# STM32_Peripherals.net
KiCad netlist of a schematic drawn in Altium Designer
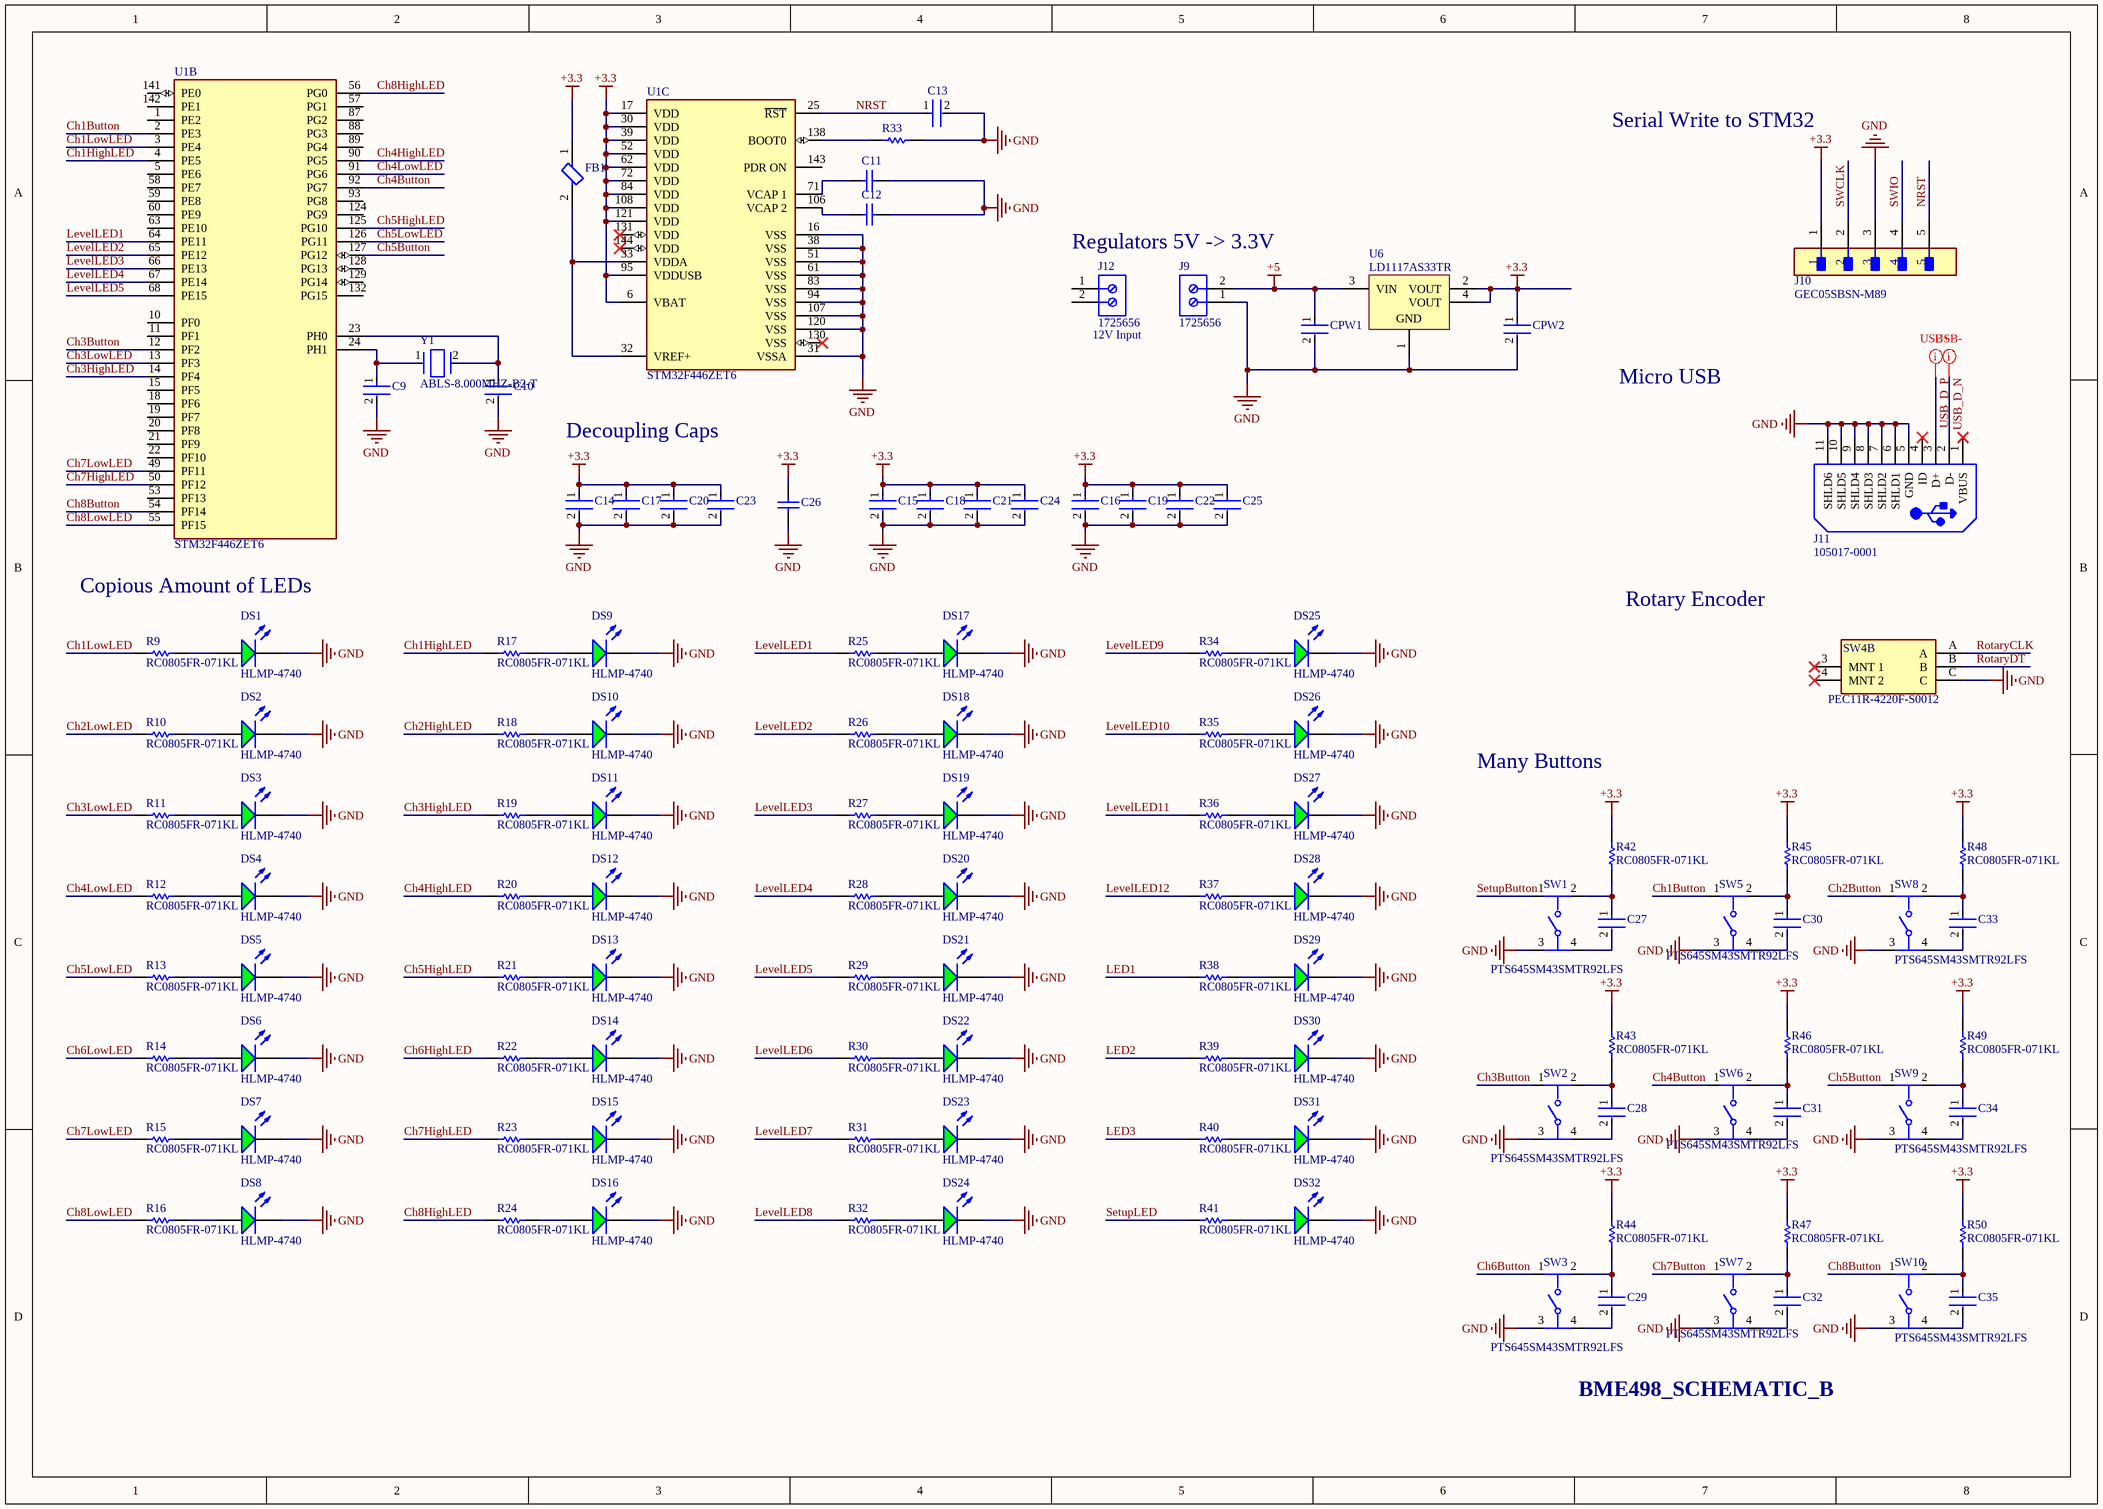
[diagram p0: STM32_Peripherals.SchDoc]

(export (version "E")
  (design (tool "Eeschema 10.0.6"))
  (components
    (comp (ref "C9")
      (value "C0805C439C5GACTU")
      (footprint "FP-C0805C-DN-MFG")
      (description "CAP CER 4.3PF 50V NP0 0805")
      (fields
        (field (name "OCTOPART") "https://octopart.com/c0805c439c5gactu-kemet-9144293")
        (field (name "MANUFACTURER") "KEMET")
      )
      (libsource (lib "Altium Content Vault") (part "b4654b650e69147ec39a6b967a45e02"))
    )
    (comp (ref "C10")
      (value "C0805C439C5GACTU")
      (footprint "FP-C0805C-DN-MFG")
      (description "CAP CER 4.3PF 50V NP0 0805")
      (fields
        (field (name "OCTOPART") "https://octopart.com/c0805c439c5gactu-kemet-9144293")
        (field (name "MANUFACTURER") "KEMET")
      )
      (libsource (lib "Altium Content Vault") (part "b4654b650e69147ec39a6b967a45e02"))
    )
    (comp (ref "C11")
      (value "GRM21BR71C225KA12L")
      (footprint "CAPC2013X135X50ML10T20")
      (fields (field (name "MANUFACTURER") "Murata"))
      (libsource (lib "Altium Content Vault") (part "CAP"))
    )
    (comp (ref "C12")
      (value "GRM21BR71C225KA12L")
      (footprint "CAPC2013X135X50ML10T20")
      (fields (field (name "MANUFACTURER") "Murata"))
      (libsource (lib "Altium Content Vault") (part "CAP"))
    )
    (comp (ref "C13")
      (value "CC0805KRX7R9BB104")
      (footprint "FP-CC0805-0_85-MFG")
      (description "CAP CER 0.1UF 50V X7R 0805")
      (fields (field (name "TOLERANCE") "0.1") (field (name "MANUFACTURER") "Yageo"))
      (libsource (lib "Altium Content Vault") (part "11868f565c42a9108669ba33697ecf6"))
    )
    (comp (ref "C14")
      (value "CC0805KRX7R9BB104")
      (footprint "FP-CC0805-0_85-MFG")
      (description "CAP CER 0.1UF 50V X7R 0805")
      (fields (field (name "TOLERANCE") "0.1") (field (name "MANUFACTURER") "Yageo"))
      (libsource (lib "Altium Content Vault") (part "11868f565c42a9108669ba33697ecf6"))
    )
    (comp (ref "C15")
      (value "CC0805KRX7R9BB104")
      (footprint "FP-CC0805-0_85-MFG")
      (description "CAP CER 0.1UF 50V X7R 0805")
      (fields (field (name "TOLERANCE") "0.1") (field (name "MANUFACTURER") "Yageo"))
      (libsource (lib "Altium Content Vault") (part "11868f565c42a9108669ba33697ecf6"))
    )
    (comp (ref "C16")
      (value "CC0805KRX7R9BB104")
      (footprint "FP-CC0805-0_85-MFG")
      (description "CAP CER 0.1UF 50V X7R 0805")
      (fields (field (name "TOLERANCE") "0.1") (field (name "MANUFACTURER") "Yageo"))
      (libsource (lib "Altium Content Vault") (part "11868f565c42a9108669ba33697ecf6"))
    )
    (comp (ref "C17")
      (value "CC0805KRX7R9BB104")
      (footprint "FP-CC0805-0_85-MFG")
      (description "CAP CER 0.1UF 50V X7R 0805")
      (fields (field (name "TOLERANCE") "0.1") (field (name "MANUFACTURER") "Yageo"))
      (libsource (lib "Altium Content Vault") (part "11868f565c42a9108669ba33697ecf6"))
    )
    (comp (ref "C18")
      (value "CC0805KRX7R9BB104")
      (footprint "FP-CC0805-0_85-MFG")
      (description "CAP CER 0.1UF 50V X7R 0805")
      (fields (field (name "TOLERANCE") "0.1") (field (name "MANUFACTURER") "Yageo"))
      (libsource (lib "Altium Content Vault") (part "11868f565c42a9108669ba33697ecf6"))
    )
    (comp (ref "C19")
      (value "CC0805KRX7R9BB104")
      (footprint "FP-CC0805-0_85-MFG")
      (description "CAP CER 0.1UF 50V X7R 0805")
      (fields (field (name "TOLERANCE") "0.1") (field (name "MANUFACTURER") "Yageo"))
      (libsource (lib "Altium Content Vault") (part "11868f565c42a9108669ba33697ecf6"))
    )
    (comp (ref "C20")
      (value "CC0805KRX7R9BB104")
      (footprint "FP-CC0805-0_85-MFG")
      (description "CAP CER 0.1UF 50V X7R 0805")
      (fields (field (name "TOLERANCE") "0.1") (field (name "MANUFACTURER") "Yageo"))
      (libsource (lib "Altium Content Vault") (part "11868f565c42a9108669ba33697ecf6"))
    )
    (comp (ref "C21")
      (value "CC0805KRX7R9BB104")
      (footprint "FP-CC0805-0_85-MFG")
      (description "CAP CER 0.1UF 50V X7R 0805")
      (fields (field (name "TOLERANCE") "0.1") (field (name "MANUFACTURER") "Yageo"))
      (libsource (lib "Altium Content Vault") (part "11868f565c42a9108669ba33697ecf6"))
    )
    (comp (ref "C22")
      (value "CC0805KRX7R9BB104")
      (footprint "FP-CC0805-0_85-MFG")
      (description "CAP CER 0.1UF 50V X7R 0805")
      (fields (field (name "TOLERANCE") "0.1") (field (name "MANUFACTURER") "Yageo"))
      (libsource (lib "Altium Content Vault") (part "11868f565c42a9108669ba33697ecf6"))
    )
    (comp (ref "C23")
      (value "CC0805KRX7R9BB104")
      (footprint "FP-CC0805-0_85-MFG")
      (description "CAP CER 0.1UF 50V X7R 0805")
      (fields (field (name "TOLERANCE") "0.1") (field (name "MANUFACTURER") "Yageo"))
      (libsource (lib "Altium Content Vault") (part "11868f565c42a9108669ba33697ecf6"))
    )
    (comp (ref "C24")
      (value "CC0805KRX7R9BB104")
      (footprint "FP-CC0805-0_85-MFG")
      (description "CAP CER 0.1UF 50V X7R 0805")
      (fields (field (name "TOLERANCE") "0.1") (field (name "MANUFACTURER") "Yageo"))
      (libsource (lib "Altium Content Vault") (part "11868f565c42a9108669ba33697ecf6"))
    )
    (comp (ref "C25")
      (value "CC0805KRX7R9BB104")
      (footprint "FP-CC0805-0_85-MFG")
      (description "CAP CER 0.1UF 50V X7R 0805")
      (fields (field (name "TOLERANCE") "0.1") (field (name "MANUFACTURER") "Yageo"))
      (libsource (lib "Altium Content Vault") (part "11868f565c42a9108669ba33697ecf6"))
    )
    (comp (ref "C26")
      (value "GRM21BR61C475KA88L")
      (footprint "CAPC2013X135X45LL10T25")
      (description "Chip Capacitor, 4.7 uF, +/- 10%, 16 V, -55 to 85 degC, 0805 (2012 Metric), RoHS, Tape and Reel")
      (fields (field (name "TOLERANCE") "10%"))
      (libsource (lib "Altium Content Vault") (part "CAP-NP-2"))
    )
    (comp (ref "C27")
      (value "CC0805KRX7R9BB104")
      (footprint "FP-CC0805-0_85-MFG")
      (description "CAP CER 0.1UF 50V X7R 0805")
      (fields (field (name "TOLERANCE") "0.1") (field (name "MANUFACTURER") "Yageo"))
      (libsource (lib "Altium Content Vault") (part "11868f565c42a9108669ba33697ecf6"))
    )
    (comp (ref "C28")
      (value "CC0805KRX7R9BB104")
      (footprint "FP-CC0805-0_85-MFG")
      (description "CAP CER 0.1UF 50V X7R 0805")
      (fields (field (name "TOLERANCE") "0.1") (field (name "MANUFACTURER") "Yageo"))
      (libsource (lib "Altium Content Vault") (part "11868f565c42a9108669ba33697ecf6"))
    )
    (comp (ref "C29")
      (value "CC0805KRX7R9BB104")
      (footprint "FP-CC0805-0_85-MFG")
      (description "CAP CER 0.1UF 50V X7R 0805")
      (fields (field (name "TOLERANCE") "0.1") (field (name "MANUFACTURER") "Yageo"))
      (libsource (lib "Altium Content Vault") (part "11868f565c42a9108669ba33697ecf6"))
    )
    (comp (ref "C30")
      (value "CC0805KRX7R9BB104")
      (footprint "FP-CC0805-0_85-MFG")
      (description "CAP CER 0.1UF 50V X7R 0805")
      (fields (field (name "TOLERANCE") "0.1") (field (name "MANUFACTURER") "Yageo"))
      (libsource (lib "Altium Content Vault") (part "11868f565c42a9108669ba33697ecf6"))
    )
    (comp (ref "C31")
      (value "CC0805KRX7R9BB104")
      (footprint "FP-CC0805-0_85-MFG")
      (description "CAP CER 0.1UF 50V X7R 0805")
      (fields (field (name "TOLERANCE") "0.1") (field (name "MANUFACTURER") "Yageo"))
      (libsource (lib "Altium Content Vault") (part "11868f565c42a9108669ba33697ecf6"))
    )
    (comp (ref "C32")
      (value "CC0805KRX7R9BB104")
      (footprint "FP-CC0805-0_85-MFG")
      (description "CAP CER 0.1UF 50V X7R 0805")
      (fields (field (name "TOLERANCE") "0.1") (field (name "MANUFACTURER") "Yageo"))
      (libsource (lib "Altium Content Vault") (part "11868f565c42a9108669ba33697ecf6"))
    )
    (comp (ref "C33")
      (value "CC0805KRX7R9BB104")
      (footprint "FP-CC0805-0_85-MFG")
      (description "CAP CER 0.1UF 50V X7R 0805")
      (fields (field (name "TOLERANCE") "0.1") (field (name "MANUFACTURER") "Yageo"))
      (libsource (lib "Altium Content Vault") (part "11868f565c42a9108669ba33697ecf6"))
    )
    (comp (ref "C34")
      (value "CC0805KRX7R9BB104")
      (footprint "FP-CC0805-0_85-MFG")
      (description "CAP CER 0.1UF 50V X7R 0805")
      (fields (field (name "TOLERANCE") "0.1") (field (name "MANUFACTURER") "Yageo"))
      (libsource (lib "Altium Content Vault") (part "11868f565c42a9108669ba33697ecf6"))
    )
    (comp (ref "C35")
      (value "CC0805KRX7R9BB104")
      (footprint "FP-CC0805-0_85-MFG")
      (description "CAP CER 0.1UF 50V X7R 0805")
      (fields (field (name "TOLERANCE") "0.1") (field (name "MANUFACTURER") "Yageo"))
      (libsource (lib "Altium Content Vault") (part "11868f565c42a9108669ba33697ecf6"))
    )
    (comp (ref "CPW1")
      (value "CC0805KRX7R9BB104")
      (footprint "FP-CC0805-0_85-MFG")
      (description "CAP CER 0.1UF 50V X7R 0805")
      (fields (field (name "TOLERANCE") "0.1") (field (name "MANUFACTURER") "Yageo"))
      (libsource (lib "Altium Content Vault") (part "11868f565c42a9108669ba33697ecf6"))
    )
    (comp (ref "CPW2")
      (value "CC0805KRX7R9BB104")
      (footprint "FP-CC0805-0_85-MFG")
      (description "CAP CER 0.1UF 50V X7R 0805")
      (fields (field (name "TOLERANCE") "0.1") (field (name "MANUFACTURER") "Yageo"))
      (libsource (lib "Altium Content Vault") (part "11868f565c42a9108669ba33697ecf6"))
    )
    (comp (ref "DS1")
      (value "HLMP-4740")
      (footprint "AVAG-HLMP-4740")
      (description "T-1 3/4 (5 mm) Low Current LED Lamp, Green, 1.9 V, -20 to 100 degC, 2-Pin THD, RoHS, Bulk")
      (fields (field (name "MANUFACTURER") "AvagoTechnologies"))
      (libsource (lib "Altium Content Vault") (part "LED-GREEN-AK-2"))
    )
    (comp (ref "DS2")
      (value "HLMP-4740")
      (footprint "AVAG-HLMP-4740")
      (description "T-1 3/4 (5 mm) Low Current LED Lamp, Green, 1.9 V, -20 to 100 degC, 2-Pin THD, RoHS, Bulk")
      (fields (field (name "MANUFACTURER") "AvagoTechnologies"))
      (libsource (lib "Altium Content Vault") (part "LED-GREEN-AK-2"))
    )
    (comp (ref "DS3")
      (value "HLMP-4740")
      (footprint "AVAG-HLMP-4740")
      (description "T-1 3/4 (5 mm) Low Current LED Lamp, Green, 1.9 V, -20 to 100 degC, 2-Pin THD, RoHS, Bulk")
      (fields (field (name "MANUFACTURER") "AvagoTechnologies"))
      (libsource (lib "Altium Content Vault") (part "LED-GREEN-AK-2"))
    )
    (comp (ref "DS4")
      (value "HLMP-4740")
      (footprint "AVAG-HLMP-4740")
      (description "T-1 3/4 (5 mm) Low Current LED Lamp, Green, 1.9 V, -20 to 100 degC, 2-Pin THD, RoHS, Bulk")
      (fields (field (name "MANUFACTURER") "AvagoTechnologies"))
      (libsource (lib "Altium Content Vault") (part "LED-GREEN-AK-2"))
    )
    (comp (ref "DS5")
      (value "HLMP-4740")
      (footprint "AVAG-HLMP-4740")
      (description "T-1 3/4 (5 mm) Low Current LED Lamp, Green, 1.9 V, -20 to 100 degC, 2-Pin THD, RoHS, Bulk")
      (fields (field (name "MANUFACTURER") "AvagoTechnologies"))
      (libsource (lib "Altium Content Vault") (part "LED-GREEN-AK-2"))
    )
    (comp (ref "DS6")
      (value "HLMP-4740")
      (footprint "AVAG-HLMP-4740")
      (description "T-1 3/4 (5 mm) Low Current LED Lamp, Green, 1.9 V, -20 to 100 degC, 2-Pin THD, RoHS, Bulk")
      (fields (field (name "MANUFACTURER") "AvagoTechnologies"))
      (libsource (lib "Altium Content Vault") (part "LED-GREEN-AK-2"))
    )
    (comp (ref "DS7")
      (value "HLMP-4740")
      (footprint "AVAG-HLMP-4740")
      (description "T-1 3/4 (5 mm) Low Current LED Lamp, Green, 1.9 V, -20 to 100 degC, 2-Pin THD, RoHS, Bulk")
      (fields (field (name "MANUFACTURER") "AvagoTechnologies"))
      (libsource (lib "Altium Content Vault") (part "LED-GREEN-AK-2"))
    )
    (comp (ref "DS8")
      (value "HLMP-4740")
      (footprint "AVAG-HLMP-4740")
      (description "T-1 3/4 (5 mm) Low Current LED Lamp, Green, 1.9 V, -20 to 100 degC, 2-Pin THD, RoHS, Bulk")
      (fields (field (name "MANUFACTURER") "AvagoTechnologies"))
      (libsource (lib "Altium Content Vault") (part "LED-GREEN-AK-2"))
    )
    (comp (ref "DS9")
      (value "HLMP-4740")
      (footprint "AVAG-HLMP-4740")
      (description "T-1 3/4 (5 mm) Low Current LED Lamp, Green, 1.9 V, -20 to 100 degC, 2-Pin THD, RoHS, Bulk")
      (fields (field (name "MANUFACTURER") "AvagoTechnologies"))
      (libsource (lib "Altium Content Vault") (part "LED-GREEN-AK-2"))
    )
    (comp (ref "DS10")
      (value "HLMP-4740")
      (footprint "AVAG-HLMP-4740")
      (description "T-1 3/4 (5 mm) Low Current LED Lamp, Green, 1.9 V, -20 to 100 degC, 2-Pin THD, RoHS, Bulk")
      (fields (field (name "MANUFACTURER") "AvagoTechnologies"))
      (libsource (lib "Altium Content Vault") (part "LED-GREEN-AK-2"))
    )
    (comp (ref "DS11")
      (value "HLMP-4740")
      (footprint "AVAG-HLMP-4740")
      (description "T-1 3/4 (5 mm) Low Current LED Lamp, Green, 1.9 V, -20 to 100 degC, 2-Pin THD, RoHS, Bulk")
      (fields (field (name "MANUFACTURER") "AvagoTechnologies"))
      (libsource (lib "Altium Content Vault") (part "LED-GREEN-AK-2"))
    )
    (comp (ref "DS12")
      (value "HLMP-4740")
      (footprint "AVAG-HLMP-4740")
      (description "T-1 3/4 (5 mm) Low Current LED Lamp, Green, 1.9 V, -20 to 100 degC, 2-Pin THD, RoHS, Bulk")
      (fields (field (name "MANUFACTURER") "AvagoTechnologies"))
      (libsource (lib "Altium Content Vault") (part "LED-GREEN-AK-2"))
    )
    (comp (ref "DS13")
      (value "HLMP-4740")
      (footprint "AVAG-HLMP-4740")
      (description "T-1 3/4 (5 mm) Low Current LED Lamp, Green, 1.9 V, -20 to 100 degC, 2-Pin THD, RoHS, Bulk")
      (fields (field (name "MANUFACTURER") "AvagoTechnologies"))
      (libsource (lib "Altium Content Vault") (part "LED-GREEN-AK-2"))
    )
    (comp (ref "DS14")
      (value "HLMP-4740")
      (footprint "AVAG-HLMP-4740")
      (description "T-1 3/4 (5 mm) Low Current LED Lamp, Green, 1.9 V, -20 to 100 degC, 2-Pin THD, RoHS, Bulk")
      (fields (field (name "MANUFACTURER") "AvagoTechnologies"))
      (libsource (lib "Altium Content Vault") (part "LED-GREEN-AK-2"))
    )
    (comp (ref "DS15")
      (value "HLMP-4740")
      (footprint "AVAG-HLMP-4740")
      (description "T-1 3/4 (5 mm) Low Current LED Lamp, Green, 1.9 V, -20 to 100 degC, 2-Pin THD, RoHS, Bulk")
      (fields (field (name "MANUFACTURER") "AvagoTechnologies"))
      (libsource (lib "Altium Content Vault") (part "LED-GREEN-AK-2"))
    )
    (comp (ref "DS16")
      (value "HLMP-4740")
      (footprint "AVAG-HLMP-4740")
      (description "T-1 3/4 (5 mm) Low Current LED Lamp, Green, 1.9 V, -20 to 100 degC, 2-Pin THD, RoHS, Bulk")
      (fields (field (name "MANUFACTURER") "AvagoTechnologies"))
      (libsource (lib "Altium Content Vault") (part "LED-GREEN-AK-2"))
    )
    (comp (ref "DS17")
      (value "HLMP-4740")
      (footprint "AVAG-HLMP-4740")
      (description "T-1 3/4 (5 mm) Low Current LED Lamp, Green, 1.9 V, -20 to 100 degC, 2-Pin THD, RoHS, Bulk")
      (fields (field (name "MANUFACTURER") "AvagoTechnologies"))
      (libsource (lib "Altium Content Vault") (part "LED-GREEN-AK-2"))
    )
    (comp (ref "DS18")
      (value "HLMP-4740")
      (footprint "AVAG-HLMP-4740")
      (description "T-1 3/4 (5 mm) Low Current LED Lamp, Green, 1.9 V, -20 to 100 degC, 2-Pin THD, RoHS, Bulk")
      (fields (field (name "MANUFACTURER") "AvagoTechnologies"))
      (libsource (lib "Altium Content Vault") (part "LED-GREEN-AK-2"))
    )
    (comp (ref "DS19")
      (value "HLMP-4740")
      (footprint "AVAG-HLMP-4740")
      (description "T-1 3/4 (5 mm) Low Current LED Lamp, Green, 1.9 V, -20 to 100 degC, 2-Pin THD, RoHS, Bulk")
      (fields (field (name "MANUFACTURER") "AvagoTechnologies"))
      (libsource (lib "Altium Content Vault") (part "LED-GREEN-AK-2"))
    )
    (comp (ref "DS20")
      (value "HLMP-4740")
      (footprint "AVAG-HLMP-4740")
      (description "T-1 3/4 (5 mm) Low Current LED Lamp, Green, 1.9 V, -20 to 100 degC, 2-Pin THD, RoHS, Bulk")
      (fields (field (name "MANUFACTURER") "AvagoTechnologies"))
      (libsource (lib "Altium Content Vault") (part "LED-GREEN-AK-2"))
    )
    (comp (ref "DS21")
      (value "HLMP-4740")
      (footprint "AVAG-HLMP-4740")
      (description "T-1 3/4 (5 mm) Low Current LED Lamp, Green, 1.9 V, -20 to 100 degC, 2-Pin THD, RoHS, Bulk")
      (fields (field (name "MANUFACTURER") "AvagoTechnologies"))
      (libsource (lib "Altium Content Vault") (part "LED-GREEN-AK-2"))
    )
    (comp (ref "DS22")
      (value "HLMP-4740")
      (footprint "AVAG-HLMP-4740")
      (description "T-1 3/4 (5 mm) Low Current LED Lamp, Green, 1.9 V, -20 to 100 degC, 2-Pin THD, RoHS, Bulk")
      (fields (field (name "MANUFACTURER") "AvagoTechnologies"))
      (libsource (lib "Altium Content Vault") (part "LED-GREEN-AK-2"))
    )
    (comp (ref "DS23")
      (value "HLMP-4740")
      (footprint "AVAG-HLMP-4740")
      (description "T-1 3/4 (5 mm) Low Current LED Lamp, Green, 1.9 V, -20 to 100 degC, 2-Pin THD, RoHS, Bulk")
      (fields (field (name "MANUFACTURER") "AvagoTechnologies"))
      (libsource (lib "Altium Content Vault") (part "LED-GREEN-AK-2"))
    )
    (comp (ref "DS24")
      (value "HLMP-4740")
      (footprint "AVAG-HLMP-4740")
      (description "T-1 3/4 (5 mm) Low Current LED Lamp, Green, 1.9 V, -20 to 100 degC, 2-Pin THD, RoHS, Bulk")
      (fields (field (name "MANUFACTURER") "AvagoTechnologies"))
      (libsource (lib "Altium Content Vault") (part "LED-GREEN-AK-2"))
    )
    (comp (ref "DS25")
      (value "HLMP-4740")
      (footprint "AVAG-HLMP-4740")
      (description "T-1 3/4 (5 mm) Low Current LED Lamp, Green, 1.9 V, -20 to 100 degC, 2-Pin THD, RoHS, Bulk")
      (fields (field (name "MANUFACTURER") "AvagoTechnologies"))
      (libsource (lib "Altium Content Vault") (part "LED-GREEN-AK-2"))
    )
    (comp (ref "DS26")
      (value "HLMP-4740")
      (footprint "AVAG-HLMP-4740")
      (description "T-1 3/4 (5 mm) Low Current LED Lamp, Green, 1.9 V, -20 to 100 degC, 2-Pin THD, RoHS, Bulk")
      (fields (field (name "MANUFACTURER") "AvagoTechnologies"))
      (libsource (lib "Altium Content Vault") (part "LED-GREEN-AK-2"))
    )
    (comp (ref "DS27")
      (value "HLMP-4740")
      (footprint "AVAG-HLMP-4740")
      (description "T-1 3/4 (5 mm) Low Current LED Lamp, Green, 1.9 V, -20 to 100 degC, 2-Pin THD, RoHS, Bulk")
      (fields (field (name "MANUFACTURER") "AvagoTechnologies"))
      (libsource (lib "Altium Content Vault") (part "LED-GREEN-AK-2"))
    )
    (comp (ref "DS28")
      (value "HLMP-4740")
      (footprint "AVAG-HLMP-4740")
      (description "T-1 3/4 (5 mm) Low Current LED Lamp, Green, 1.9 V, -20 to 100 degC, 2-Pin THD, RoHS, Bulk")
      (fields (field (name "MANUFACTURER") "AvagoTechnologies"))
      (libsource (lib "Altium Content Vault") (part "LED-GREEN-AK-2"))
    )
    (comp (ref "DS29")
      (value "HLMP-4740")
      (footprint "AVAG-HLMP-4740")
      (description "T-1 3/4 (5 mm) Low Current LED Lamp, Green, 1.9 V, -20 to 100 degC, 2-Pin THD, RoHS, Bulk")
      (fields (field (name "MANUFACTURER") "AvagoTechnologies"))
      (libsource (lib "Altium Content Vault") (part "LED-GREEN-AK-2"))
    )
    (comp (ref "DS30")
      (value "HLMP-4740")
      (footprint "AVAG-HLMP-4740")
      (description "T-1 3/4 (5 mm) Low Current LED Lamp, Green, 1.9 V, -20 to 100 degC, 2-Pin THD, RoHS, Bulk")
      (fields (field (name "MANUFACTURER") "AvagoTechnologies"))
      (libsource (lib "Altium Content Vault") (part "LED-GREEN-AK-2"))
    )
    (comp (ref "DS31")
      (value "HLMP-4740")
      (footprint "AVAG-HLMP-4740")
      (description "T-1 3/4 (5 mm) Low Current LED Lamp, Green, 1.9 V, -20 to 100 degC, 2-Pin THD, RoHS, Bulk")
      (fields (field (name "MANUFACTURER") "AvagoTechnologies"))
      (libsource (lib "Altium Content Vault") (part "LED-GREEN-AK-2"))
    )
    (comp (ref "DS32")
      (value "HLMP-4740")
      (footprint "AVAG-HLMP-4740")
      (description "T-1 3/4 (5 mm) Low Current LED Lamp, Green, 1.9 V, -20 to 100 degC, 2-Pin THD, RoHS, Bulk")
      (fields (field (name "MANUFACTURER") "AvagoTechnologies"))
      (libsource (lib "Altium Content Vault") (part "LED-GREEN-AK-2"))
    )
    (comp (ref "FB1")
      (value "BLM21SP181SN1D")
      (footprint "FP-BLM21-0_2-t0_85-e0_5-IPC_A")
      (description "Chip Ferrite Bead, 0805, 180Ω @ 100MHz, 0.02Ω, 25%, 4A")
      (libsource (lib "Altium Content Vault") (part "5f30dd21d616792df468990f7003faa"))
    )
    (comp (ref "J9")
      (value "1725656")
      (footprint "PHOE-1725656-2")
      (description "Male Header, Pitch 2.54 mm, 1 x 2 Position, Height 9 mm, Tail Length 3.5 mm")
      (fields (field (name "MANUFACTURER") "Phoenix Contact"))
      (libsource (lib "Altium Content Vault") (part "CN-1P-F-TB2"))
    )
    (comp (ref "J10")
      (value "GEC05SBSN-M89")
      (footprint "FP-GEC05SBSN-M89-MFG")
      (description "CONN HEADER SMD R/A 5POS 2.54MM")
      (libsource (lib "Altium Content Vault") (part "051ac7c1f60a91215dd69c4e70fad1a"))
    )
    (comp (ref "J11")
      (value "105017-0001")
      (footprint "USB-MICRO-B_V")
      (fields (field (name "MANUFACTURER") "Molex"))
      (libsource (lib "Altium Content Vault") (part "USB-5-6SHLD"))
    )
    (comp (ref "J12")
      (value "1725656")
      (footprint "PHOE-1725656-2")
      (description "Male Header, Pitch 2.54 mm, 1 x 2 Position, Height 9 mm, Tail Length 3.5 mm")
      (fields (field (name "MANUFACTURER") "Phoenix Contact"))
      (libsource (lib "Altium Content Vault") (part "CN-1P-F-TB2"))
    )
    (comp (ref "R9")
      (value "RC0805FR-071KL")
      (footprint "RESC2013X60X35ML10T20")
      (description "Chip Resistor, 1 KOhm, +/- 1%, 125 mW, -55 to 155 degC, 0805 (2012 Metric), RoHS, Tape and Reel")
      (fields (field (name "TOLERANCE") "1%") (field (name "MANUFACTURER") "Yageo"))
      (libsource (lib "Altium Content Vault") (part "RES-2"))
    )
    (comp (ref "R10")
      (value "RC0805FR-071KL")
      (footprint "RESC2013X60X35ML10T20")
      (description "Chip Resistor, 1 KOhm, +/- 1%, 125 mW, -55 to 155 degC, 0805 (2012 Metric), RoHS, Tape and Reel")
      (fields (field (name "TOLERANCE") "1%") (field (name "MANUFACTURER") "Yageo"))
      (libsource (lib "Altium Content Vault") (part "RES-2"))
    )
    (comp (ref "R11")
      (value "RC0805FR-071KL")
      (footprint "RESC2013X60X35ML10T20")
      (description "Chip Resistor, 1 KOhm, +/- 1%, 125 mW, -55 to 155 degC, 0805 (2012 Metric), RoHS, Tape and Reel")
      (fields (field (name "TOLERANCE") "1%") (field (name "MANUFACTURER") "Yageo"))
      (libsource (lib "Altium Content Vault") (part "RES-2"))
    )
    (comp (ref "R12")
      (value "RC0805FR-071KL")
      (footprint "RESC2013X60X35ML10T20")
      (description "Chip Resistor, 1 KOhm, +/- 1%, 125 mW, -55 to 155 degC, 0805 (2012 Metric), RoHS, Tape and Reel")
      (fields (field (name "TOLERANCE") "1%") (field (name "MANUFACTURER") "Yageo"))
      (libsource (lib "Altium Content Vault") (part "RES-2"))
    )
    (comp (ref "R13")
      (value "RC0805FR-071KL")
      (footprint "RESC2013X60X35ML10T20")
      (description "Chip Resistor, 1 KOhm, +/- 1%, 125 mW, -55 to 155 degC, 0805 (2012 Metric), RoHS, Tape and Reel")
      (fields (field (name "TOLERANCE") "1%") (field (name "MANUFACTURER") "Yageo"))
      (libsource (lib "Altium Content Vault") (part "RES-2"))
    )
    (comp (ref "R14")
      (value "RC0805FR-071KL")
      (footprint "RESC2013X60X35ML10T20")
      (description "Chip Resistor, 1 KOhm, +/- 1%, 125 mW, -55 to 155 degC, 0805 (2012 Metric), RoHS, Tape and Reel")
      (fields (field (name "TOLERANCE") "1%") (field (name "MANUFACTURER") "Yageo"))
      (libsource (lib "Altium Content Vault") (part "RES-2"))
    )
    (comp (ref "R15")
      (value "RC0805FR-071KL")
      (footprint "RESC2013X60X35ML10T20")
      (description "Chip Resistor, 1 KOhm, +/- 1%, 125 mW, -55 to 155 degC, 0805 (2012 Metric), RoHS, Tape and Reel")
      (fields (field (name "TOLERANCE") "1%") (field (name "MANUFACTURER") "Yageo"))
      (libsource (lib "Altium Content Vault") (part "RES-2"))
    )
    (comp (ref "R16")
      (value "RC0805FR-071KL")
      (footprint "RESC2013X60X35ML10T20")
      (description "Chip Resistor, 1 KOhm, +/- 1%, 125 mW, -55 to 155 degC, 0805 (2012 Metric), RoHS, Tape and Reel")
      (fields (field (name "TOLERANCE") "1%") (field (name "MANUFACTURER") "Yageo"))
      (libsource (lib "Altium Content Vault") (part "RES-2"))
    )
    (comp (ref "R17")
      (value "RC0805FR-071KL")
      (footprint "RESC2013X60X35ML10T20")
      (description "Chip Resistor, 1 KOhm, +/- 1%, 125 mW, -55 to 155 degC, 0805 (2012 Metric), RoHS, Tape and Reel")
      (fields (field (name "TOLERANCE") "1%") (field (name "MANUFACTURER") "Yageo"))
      (libsource (lib "Altium Content Vault") (part "RES-2"))
    )
    (comp (ref "R18")
      (value "RC0805FR-071KL")
      (footprint "RESC2013X60X35ML10T20")
      (description "Chip Resistor, 1 KOhm, +/- 1%, 125 mW, -55 to 155 degC, 0805 (2012 Metric), RoHS, Tape and Reel")
      (fields (field (name "TOLERANCE") "1%") (field (name "MANUFACTURER") "Yageo"))
      (libsource (lib "Altium Content Vault") (part "RES-2"))
    )
    (comp (ref "R19")
      (value "RC0805FR-071KL")
      (footprint "RESC2013X60X35ML10T20")
      (description "Chip Resistor, 1 KOhm, +/- 1%, 125 mW, -55 to 155 degC, 0805 (2012 Metric), RoHS, Tape and Reel")
      (fields (field (name "TOLERANCE") "1%") (field (name "MANUFACTURER") "Yageo"))
      (libsource (lib "Altium Content Vault") (part "RES-2"))
    )
    (comp (ref "R20")
      (value "RC0805FR-071KL")
      (footprint "RESC2013X60X35ML10T20")
      (description "Chip Resistor, 1 KOhm, +/- 1%, 125 mW, -55 to 155 degC, 0805 (2012 Metric), RoHS, Tape and Reel")
      (fields (field (name "TOLERANCE") "1%") (field (name "MANUFACTURER") "Yageo"))
      (libsource (lib "Altium Content Vault") (part "RES-2"))
    )
    (comp (ref "R21")
      (value "RC0805FR-071KL")
      (footprint "RESC2013X60X35ML10T20")
      (description "Chip Resistor, 1 KOhm, +/- 1%, 125 mW, -55 to 155 degC, 0805 (2012 Metric), RoHS, Tape and Reel")
      (fields (field (name "TOLERANCE") "1%") (field (name "MANUFACTURER") "Yageo"))
      (libsource (lib "Altium Content Vault") (part "RES-2"))
    )
    (comp (ref "R22")
      (value "RC0805FR-071KL")
      (footprint "RESC2013X60X35ML10T20")
      (description "Chip Resistor, 1 KOhm, +/- 1%, 125 mW, -55 to 155 degC, 0805 (2012 Metric), RoHS, Tape and Reel")
      (fields (field (name "TOLERANCE") "1%") (field (name "MANUFACTURER") "Yageo"))
      (libsource (lib "Altium Content Vault") (part "RES-2"))
    )
    (comp (ref "R23")
      (value "RC0805FR-071KL")
      (footprint "RESC2013X60X35ML10T20")
      (description "Chip Resistor, 1 KOhm, +/- 1%, 125 mW, -55 to 155 degC, 0805 (2012 Metric), RoHS, Tape and Reel")
      (fields (field (name "TOLERANCE") "1%") (field (name "MANUFACTURER") "Yageo"))
      (libsource (lib "Altium Content Vault") (part "RES-2"))
    )
    (comp (ref "R24")
      (value "RC0805FR-071KL")
      (footprint "RESC2013X60X35ML10T20")
      (description "Chip Resistor, 1 KOhm, +/- 1%, 125 mW, -55 to 155 degC, 0805 (2012 Metric), RoHS, Tape and Reel")
      (fields (field (name "TOLERANCE") "1%") (field (name "MANUFACTURER") "Yageo"))
      (libsource (lib "Altium Content Vault") (part "RES-2"))
    )
    (comp (ref "R25")
      (value "RC0805FR-071KL")
      (footprint "RESC2013X60X35ML10T20")
      (description "Chip Resistor, 1 KOhm, +/- 1%, 125 mW, -55 to 155 degC, 0805 (2012 Metric), RoHS, Tape and Reel")
      (fields (field (name "TOLERANCE") "1%") (field (name "MANUFACTURER") "Yageo"))
      (libsource (lib "Altium Content Vault") (part "RES-2"))
    )
    (comp (ref "R26")
      (value "RC0805FR-071KL")
      (footprint "RESC2013X60X35ML10T20")
      (description "Chip Resistor, 1 KOhm, +/- 1%, 125 mW, -55 to 155 degC, 0805 (2012 Metric), RoHS, Tape and Reel")
      (fields (field (name "TOLERANCE") "1%") (field (name "MANUFACTURER") "Yageo"))
      (libsource (lib "Altium Content Vault") (part "RES-2"))
    )
    (comp (ref "R27")
      (value "RC0805FR-071KL")
      (footprint "RESC2013X60X35ML10T20")
      (description "Chip Resistor, 1 KOhm, +/- 1%, 125 mW, -55 to 155 degC, 0805 (2012 Metric), RoHS, Tape and Reel")
      (fields (field (name "TOLERANCE") "1%") (field (name "MANUFACTURER") "Yageo"))
      (libsource (lib "Altium Content Vault") (part "RES-2"))
    )
    (comp (ref "R28")
      (value "RC0805FR-071KL")
      (footprint "RESC2013X60X35ML10T20")
      (description "Chip Resistor, 1 KOhm, +/- 1%, 125 mW, -55 to 155 degC, 0805 (2012 Metric), RoHS, Tape and Reel")
      (fields (field (name "TOLERANCE") "1%") (field (name "MANUFACTURER") "Yageo"))
      (libsource (lib "Altium Content Vault") (part "RES-2"))
    )
    (comp (ref "R29")
      (value "RC0805FR-071KL")
      (footprint "RESC2013X60X35ML10T20")
      (description "Chip Resistor, 1 KOhm, +/- 1%, 125 mW, -55 to 155 degC, 0805 (2012 Metric), RoHS, Tape and Reel")
      (fields (field (name "TOLERANCE") "1%") (field (name "MANUFACTURER") "Yageo"))
      (libsource (lib "Altium Content Vault") (part "RES-2"))
    )
    (comp (ref "R30")
      (value "RC0805FR-071KL")
      (footprint "RESC2013X60X35ML10T20")
      (description "Chip Resistor, 1 KOhm, +/- 1%, 125 mW, -55 to 155 degC, 0805 (2012 Metric), RoHS, Tape and Reel")
      (fields (field (name "TOLERANCE") "1%") (field (name "MANUFACTURER") "Yageo"))
      (libsource (lib "Altium Content Vault") (part "RES-2"))
    )
    (comp (ref "R31")
      (value "RC0805FR-071KL")
      (footprint "RESC2013X60X35ML10T20")
      (description "Chip Resistor, 1 KOhm, +/- 1%, 125 mW, -55 to 155 degC, 0805 (2012 Metric), RoHS, Tape and Reel")
      (fields (field (name "TOLERANCE") "1%") (field (name "MANUFACTURER") "Yageo"))
      (libsource (lib "Altium Content Vault") (part "RES-2"))
    )
    (comp (ref "R32")
      (value "RC0805FR-071KL")
      (footprint "RESC2013X60X35ML10T20")
      (description "Chip Resistor, 1 KOhm, +/- 1%, 125 mW, -55 to 155 degC, 0805 (2012 Metric), RoHS, Tape and Reel")
      (fields (field (name "TOLERANCE") "1%") (field (name "MANUFACTURER") "Yageo"))
      (libsource (lib "Altium Content Vault") (part "RES-2"))
    )
    (comp (ref "R33")
      (value "RC0805FR-0710KL")
      (footprint "RESC2013X60X35NL10T20")
      (description "Chip Resistor, 10 KOhm, +/- 1%, 0.125 W, -55 to 155 degC, 0805 (2012 Metric), RoHS, Tape and Reel")
      (fields (field (name "MANUFACTURER") "Yageo"))
      (libsource (lib "Altium Content Vault") (part "RES-2"))
    )
    (comp (ref "R34")
      (value "RC0805FR-071KL")
      (footprint "RESC2013X60X35ML10T20")
      (description "Chip Resistor, 1 KOhm, +/- 1%, 125 mW, -55 to 155 degC, 0805 (2012 Metric), RoHS, Tape and Reel")
      (fields (field (name "TOLERANCE") "1%") (field (name "MANUFACTURER") "Yageo"))
      (libsource (lib "Altium Content Vault") (part "RES-2"))
    )
    (comp (ref "R35")
      (value "RC0805FR-071KL")
      (footprint "RESC2013X60X35ML10T20")
      (description "Chip Resistor, 1 KOhm, +/- 1%, 125 mW, -55 to 155 degC, 0805 (2012 Metric), RoHS, Tape and Reel")
      (fields (field (name "TOLERANCE") "1%") (field (name "MANUFACTURER") "Yageo"))
      (libsource (lib "Altium Content Vault") (part "RES-2"))
    )
    (comp (ref "R36")
      (value "RC0805FR-071KL")
      (footprint "RESC2013X60X35ML10T20")
      (description "Chip Resistor, 1 KOhm, +/- 1%, 125 mW, -55 to 155 degC, 0805 (2012 Metric), RoHS, Tape and Reel")
      (fields (field (name "TOLERANCE") "1%") (field (name "MANUFACTURER") "Yageo"))
      (libsource (lib "Altium Content Vault") (part "RES-2"))
    )
    (comp (ref "R37")
      (value "RC0805FR-071KL")
      (footprint "RESC2013X60X35ML10T20")
      (description "Chip Resistor, 1 KOhm, +/- 1%, 125 mW, -55 to 155 degC, 0805 (2012 Metric), RoHS, Tape and Reel")
      (fields (field (name "TOLERANCE") "1%") (field (name "MANUFACTURER") "Yageo"))
      (libsource (lib "Altium Content Vault") (part "RES-2"))
    )
    (comp (ref "R38")
      (value "RC0805FR-071KL")
      (footprint "RESC2013X60X35ML10T20")
      (description "Chip Resistor, 1 KOhm, +/- 1%, 125 mW, -55 to 155 degC, 0805 (2012 Metric), RoHS, Tape and Reel")
      (fields (field (name "TOLERANCE") "1%") (field (name "MANUFACTURER") "Yageo"))
      (libsource (lib "Altium Content Vault") (part "RES-2"))
    )
    (comp (ref "R39")
      (value "RC0805FR-071KL")
      (footprint "RESC2013X60X35ML10T20")
      (description "Chip Resistor, 1 KOhm, +/- 1%, 125 mW, -55 to 155 degC, 0805 (2012 Metric), RoHS, Tape and Reel")
      (fields (field (name "TOLERANCE") "1%") (field (name "MANUFACTURER") "Yageo"))
      (libsource (lib "Altium Content Vault") (part "RES-2"))
    )
    (comp (ref "R40")
      (value "RC0805FR-071KL")
      (footprint "RESC2013X60X35ML10T20")
      (description "Chip Resistor, 1 KOhm, +/- 1%, 125 mW, -55 to 155 degC, 0805 (2012 Metric), RoHS, Tape and Reel")
      (fields (field (name "TOLERANCE") "1%") (field (name "MANUFACTURER") "Yageo"))
      (libsource (lib "Altium Content Vault") (part "RES-2"))
    )
    (comp (ref "R41")
      (value "RC0805FR-071KL")
      (footprint "RESC2013X60X35ML10T20")
      (description "Chip Resistor, 1 KOhm, +/- 1%, 125 mW, -55 to 155 degC, 0805 (2012 Metric), RoHS, Tape and Reel")
      (fields (field (name "TOLERANCE") "1%") (field (name "MANUFACTURER") "Yageo"))
      (libsource (lib "Altium Content Vault") (part "RES-2"))
    )
    (comp (ref "R42")
      (value "RC0805FR-071KL")
      (footprint "RESC2013X60X35ML10T20")
      (description "Chip Resistor, 1 KOhm, +/- 1%, 125 mW, -55 to 155 degC, 0805 (2012 Metric), RoHS, Tape and Reel")
      (fields (field (name "TOLERANCE") "1%") (field (name "MANUFACTURER") "Yageo"))
      (libsource (lib "Altium Content Vault") (part "RES-2"))
    )
    (comp (ref "R43")
      (value "RC0805FR-071KL")
      (footprint "RESC2013X60X35ML10T20")
      (description "Chip Resistor, 1 KOhm, +/- 1%, 125 mW, -55 to 155 degC, 0805 (2012 Metric), RoHS, Tape and Reel")
      (fields (field (name "TOLERANCE") "1%") (field (name "MANUFACTURER") "Yageo"))
      (libsource (lib "Altium Content Vault") (part "RES-2"))
    )
    (comp (ref "R44")
      (value "RC0805FR-071KL")
      (footprint "RESC2013X60X35ML10T20")
      (description "Chip Resistor, 1 KOhm, +/- 1%, 125 mW, -55 to 155 degC, 0805 (2012 Metric), RoHS, Tape and Reel")
      (fields (field (name "TOLERANCE") "1%") (field (name "MANUFACTURER") "Yageo"))
      (libsource (lib "Altium Content Vault") (part "RES-2"))
    )
    (comp (ref "R45")
      (value "RC0805FR-071KL")
      (footprint "RESC2013X60X35ML10T20")
      (description "Chip Resistor, 1 KOhm, +/- 1%, 125 mW, -55 to 155 degC, 0805 (2012 Metric), RoHS, Tape and Reel")
      (fields (field (name "TOLERANCE") "1%") (field (name "MANUFACTURER") "Yageo"))
      (libsource (lib "Altium Content Vault") (part "RES-2"))
    )
    (comp (ref "R46")
      (value "RC0805FR-071KL")
      (footprint "RESC2013X60X35ML10T20")
      (description "Chip Resistor, 1 KOhm, +/- 1%, 125 mW, -55 to 155 degC, 0805 (2012 Metric), RoHS, Tape and Reel")
      (fields (field (name "TOLERANCE") "1%") (field (name "MANUFACTURER") "Yageo"))
      (libsource (lib "Altium Content Vault") (part "RES-2"))
    )
    (comp (ref "R47")
      (value "RC0805FR-071KL")
      (footprint "RESC2013X60X35ML10T20")
      (description "Chip Resistor, 1 KOhm, +/- 1%, 125 mW, -55 to 155 degC, 0805 (2012 Metric), RoHS, Tape and Reel")
      (fields (field (name "TOLERANCE") "1%") (field (name "MANUFACTURER") "Yageo"))
      (libsource (lib "Altium Content Vault") (part "RES-2"))
    )
    (comp (ref "R48")
      (value "RC0805FR-071KL")
      (footprint "RESC2013X60X35ML10T20")
      (description "Chip Resistor, 1 KOhm, +/- 1%, 125 mW, -55 to 155 degC, 0805 (2012 Metric), RoHS, Tape and Reel")
      (fields (field (name "TOLERANCE") "1%") (field (name "MANUFACTURER") "Yageo"))
      (libsource (lib "Altium Content Vault") (part "RES-2"))
    )
    (comp (ref "R49")
      (value "RC0805FR-071KL")
      (footprint "RESC2013X60X35ML10T20")
      (description "Chip Resistor, 1 KOhm, +/- 1%, 125 mW, -55 to 155 degC, 0805 (2012 Metric), RoHS, Tape and Reel")
      (fields (field (name "TOLERANCE") "1%") (field (name "MANUFACTURER") "Yageo"))
      (libsource (lib "Altium Content Vault") (part "RES-2"))
    )
    (comp (ref "R50")
      (value "RC0805FR-071KL")
      (footprint "RESC2013X60X35ML10T20")
      (description "Chip Resistor, 1 KOhm, +/- 1%, 125 mW, -55 to 155 degC, 0805 (2012 Metric), RoHS, Tape and Reel")
      (fields (field (name "TOLERANCE") "1%") (field (name "MANUFACTURER") "Yageo"))
      (libsource (lib "Altium Content Vault") (part "RES-2"))
    )
    (comp (ref "SW1")
      (value "PTS645SM43SMTR92LFS")
      (footprint "FP-PTS645SM43SMTR92LFS-MFG")
      (description "SWITCH TACTILE SPST-NO 0.05A 12V")
      (libsource (lib "Altium Content Vault") (part "1adf0dd01260c80cf25a44bfd6b99ba"))
    )
    (comp (ref "SW2")
      (value "PTS645SM43SMTR92LFS")
      (footprint "FP-PTS645SM43SMTR92LFS-MFG")
      (description "SWITCH TACTILE SPST-NO 0.05A 12V")
      (libsource (lib "Altium Content Vault") (part "1adf0dd01260c80cf25a44bfd6b99ba"))
    )
    (comp (ref "SW3")
      (value "PTS645SM43SMTR92LFS")
      (footprint "FP-PTS645SM43SMTR92LFS-MFG")
      (description "SWITCH TACTILE SPST-NO 0.05A 12V")
      (libsource (lib "Altium Content Vault") (part "1adf0dd01260c80cf25a44bfd6b99ba"))
    )
    (comp (ref "SW4")
      (value "PEC11R-4220F-S0012")
      (footprint "FP-PEC11R-4220F-S0012-MFG")
      (description "ROTARY ENCODER MECHANICAL 12PPR")
      (libsource (lib "Altium Content Vault") (part "f5a0de1f6a3fa4000440ad1e846d38a"))
    )
    (comp (ref "SW5")
      (value "PTS645SM43SMTR92LFS")
      (footprint "FP-PTS645SM43SMTR92LFS-MFG")
      (description "SWITCH TACTILE SPST-NO 0.05A 12V")
      (libsource (lib "Altium Content Vault") (part "1adf0dd01260c80cf25a44bfd6b99ba"))
    )
    (comp (ref "SW6")
      (value "PTS645SM43SMTR92LFS")
      (footprint "FP-PTS645SM43SMTR92LFS-MFG")
      (description "SWITCH TACTILE SPST-NO 0.05A 12V")
      (libsource (lib "Altium Content Vault") (part "1adf0dd01260c80cf25a44bfd6b99ba"))
    )
    (comp (ref "SW7")
      (value "PTS645SM43SMTR92LFS")
      (footprint "FP-PTS645SM43SMTR92LFS-MFG")
      (description "SWITCH TACTILE SPST-NO 0.05A 12V")
      (libsource (lib "Altium Content Vault") (part "1adf0dd01260c80cf25a44bfd6b99ba"))
    )
    (comp (ref "SW8")
      (value "PTS645SM43SMTR92LFS")
      (footprint "FP-PTS645SM43SMTR92LFS-MFG")
      (description "SWITCH TACTILE SPST-NO 0.05A 12V")
      (libsource (lib "Altium Content Vault") (part "1adf0dd01260c80cf25a44bfd6b99ba"))
    )
    (comp (ref "SW9")
      (value "PTS645SM43SMTR92LFS")
      (footprint "FP-PTS645SM43SMTR92LFS-MFG")
      (description "SWITCH TACTILE SPST-NO 0.05A 12V")
      (libsource (lib "Altium Content Vault") (part "1adf0dd01260c80cf25a44bfd6b99ba"))
    )
    (comp (ref "SW10")
      (value "PTS645SM43SMTR92LFS")
      (footprint "FP-PTS645SM43SMTR92LFS-MFG")
      (description "SWITCH TACTILE SPST-NO 0.05A 12V")
      (libsource (lib "Altium Content Vault") (part "1adf0dd01260c80cf25a44bfd6b99ba"))
    )
    (comp (ref "U1")
      (value "STM32F446ZET6")
      (footprint "FP-STM32F446ZET6-MFG")
      (description "IC MCU 32BIT 512KB FLASH 144LQFP")
      (fields
        (field (name "OCTOPART") "https://octopart.com/stm32f446zet6-stmicroelectronics-52642927")
        (field (name "MANUFACTURER") "STMicroelectronics")
      )
      (libsource (lib "Altium Content Vault") (part "a0fab8d4e0431f78458e0514a03e2d2"))
    )
    (comp (ref "U6")
      (value "LD1117AS33TR")
      (footprint "SOT-223_M")
      (description "1A, Low Drop Positive Voltage Regulator, 3.3V, 4-Pin SOT-223, Tape and Reel")
      (libsource (lib "Altium Content Vault") (part "PM-REG-LD1117-SOT4"))
    )
    (comp (ref "Y1")
      (value "ABLS-8.000MHZ-B2-T")
      (footprint "FP-ABLS-MFG")
      (description "CRYSTAL 8.0000MHZ 18PF SMD")
      (fields (field (name "TOLERANCE") "20ppm"))
      (libsource (lib "Altium Content Vault") (part "c23a69dc6c9e2f18f2079038eb95dd1"))
    )
  )
  (nets
    (net (code "1") (name "+3.3") (class "Default")
      (node (ref "C14") (pin "1") (pinfunction "1_1") (pintype "passive"))
      (node (ref "C15") (pin "1") (pinfunction "1_1") (pintype "passive"))
      (node (ref "C16") (pin "1") (pinfunction "1_1") (pintype "passive"))
      (node (ref "C17") (pin "1") (pinfunction "1_1") (pintype "passive"))
      (node (ref "C18") (pin "1") (pinfunction "1_1") (pintype "passive"))
      (node (ref "C19") (pin "1") (pinfunction "1_1") (pintype "passive"))
      (node (ref "C20") (pin "1") (pinfunction "1_1") (pintype "passive"))
      (node (ref "C21") (pin "1") (pinfunction "1_1") (pintype "passive"))
      (node (ref "C22") (pin "1") (pinfunction "1_1") (pintype "passive"))
      (node (ref "C23") (pin "1") (pinfunction "1_1") (pintype "passive"))
      (node (ref "C24") (pin "1") (pinfunction "1_1") (pintype "passive"))
      (node (ref "C25") (pin "1") (pinfunction "1_1") (pintype "passive"))
      (node (ref "C26") (pin "1") (pinfunction "1_1") (pintype "passive"))
      (node (ref "CPW2") (pin "1") (pinfunction "1_1") (pintype "passive"))
      (node (ref "FB1") (pin "1") (pinfunction "1_1") (pintype "passive"))
      (node (ref "J10") (pin "1") (pinfunction "1_1") (pintype "passive"))
      (node (ref "R42") (pin "2") (pinfunction "2_2") (pintype "passive"))
      (node (ref "R43") (pin "2") (pinfunction "2_2") (pintype "passive"))
      (node (ref "R44") (pin "2") (pinfunction "2_2") (pintype "passive"))
      (node (ref "R45") (pin "2") (pinfunction "2_2") (pintype "passive"))
      (node (ref "R46") (pin "2") (pinfunction "2_2") (pintype "passive"))
      (node (ref "R47") (pin "2") (pinfunction "2_2") (pintype "passive"))
      (node (ref "R48") (pin "2") (pinfunction "2_2") (pintype "passive"))
      (node (ref "R49") (pin "2") (pinfunction "2_2") (pintype "passive"))
      (node (ref "R50") (pin "2") (pinfunction "2_2") (pintype "passive"))
      (node (ref "U1") (pin "108") (pinfunction "VDD_108") (pintype "passive"))
      (node (ref "U1") (pin "121") (pinfunction "VDD_121") (pintype "passive"))
      (node (ref "U1") (pin "17") (pinfunction "VDD_17") (pintype "passive"))
      (node (ref "U1") (pin "30") (pinfunction "VDD_30") (pintype "passive"))
      (node (ref "U1") (pin "39") (pinfunction "VDD_39") (pintype "passive"))
      (node (ref "U1") (pin "52") (pinfunction "VDD_52") (pintype "passive"))
      (node (ref "U1") (pin "6") (pinfunction "VBAT_6") (pintype "passive"))
      (node (ref "U1") (pin "62") (pinfunction "VDD_62") (pintype "passive"))
      (node (ref "U1") (pin "72") (pinfunction "VDD_72") (pintype "passive"))
      (node (ref "U1") (pin "84") (pinfunction "VDD_84") (pintype "passive"))
      (node (ref "U1") (pin "95") (pinfunction "VDDUSB_95") (pintype "passive"))
      (node (ref "U6") (pin "2") (pinfunction "VOUT_2") (pintype "power_in"))
      (node (ref "U6") (pin "4") (pinfunction "VOUT_4") (pintype "power_in"))
    )
    (net (code "2") (name "+5") (class "Default")
      (node (ref "CPW1") (pin "1") (pinfunction "1_1") (pintype "passive"))
      (node (ref "J9") (pin "2") (pinfunction "2_2") (pintype "passive"))
      (node (ref "U6") (pin "3") (pinfunction "VIN_3") (pintype "power_in"))
    )
    (net (code "3") (name "/Ch1Button") (class "Default")
      (node (ref "SW5") (pin "1") (pinfunction "1_1") (pintype "passive"))
      (node (ref "U1") (pin "2") (pinfunction "PE3_2") (pintype "passive"))
    )
    (net (code "4") (name "/Ch1HighLED") (class "Default")
      (node (ref "R17") (pin "1") (pinfunction "1_1") (pintype "passive"))
      (node (ref "U1") (pin "4") (pinfunction "PE5_4") (pintype "passive"))
    )
    (net (code "5") (name "/Ch1LowLED") (class "Default")
      (node (ref "R9") (pin "1") (pinfunction "1_1") (pintype "passive"))
      (node (ref "U1") (pin "3") (pinfunction "PE4_3") (pintype "passive"))
    )
    (net (code "6") (name "/Ch2Button") (class "Default")
      (node (ref "SW8") (pin "1") (pinfunction "1_1") (pintype "passive"))
    )
    (net (code "7") (name "/Ch2HighLED") (class "Default")
      (node (ref "R18") (pin "1") (pinfunction "1_1") (pintype "passive"))
    )
    (net (code "8") (name "/Ch2LowLED") (class "Default")
      (node (ref "R10") (pin "1") (pinfunction "1_1") (pintype "passive"))
    )
    (net (code "9") (name "/Ch3Button") (class "Default")
      (node (ref "SW2") (pin "1") (pinfunction "1_1") (pintype "passive"))
      (node (ref "U1") (pin "12") (pinfunction "PF2_12") (pintype "passive"))
    )
    (net (code "10") (name "/Ch3HighLED") (class "Default")
      (node (ref "R19") (pin "1") (pinfunction "1_1") (pintype "passive"))
      (node (ref "U1") (pin "14") (pinfunction "PF4_14") (pintype "passive"))
    )
    (net (code "11") (name "/Ch3LowLED") (class "Default")
      (node (ref "R11") (pin "1") (pinfunction "1_1") (pintype "passive"))
      (node (ref "U1") (pin "13") (pinfunction "PF3_13") (pintype "passive"))
    )
    (net (code "12") (name "/Ch4Button") (class "Default")
      (node (ref "SW6") (pin "1") (pinfunction "1_1") (pintype "passive"))
      (node (ref "U1") (pin "92") (pinfunction "PG7_92") (pintype "passive"))
    )
    (net (code "13") (name "/Ch4HighLED") (class "Default")
      (node (ref "R20") (pin "1") (pinfunction "1_1") (pintype "passive"))
      (node (ref "U1") (pin "90") (pinfunction "PG5_90") (pintype "passive"))
    )
    (net (code "14") (name "/Ch4LowLED") (class "Default")
      (node (ref "R12") (pin "1") (pinfunction "1_1") (pintype "passive"))
      (node (ref "U1") (pin "91") (pinfunction "PG6_91") (pintype "passive"))
    )
    (net (code "15") (name "/Ch5Button") (class "Default")
      (node (ref "SW9") (pin "1") (pinfunction "1_1") (pintype "passive"))
      (node (ref "U1") (pin "127") (pinfunction "PG12_127") (pintype "bidirectional"))
    )
    (net (code "16") (name "/Ch5HighLED") (class "Default")
      (node (ref "R21") (pin "1") (pinfunction "1_1") (pintype "passive"))
      (node (ref "U1") (pin "125") (pinfunction "PG10_125") (pintype "passive"))
    )
    (net (code "17") (name "/Ch5LowLED") (class "Default")
      (node (ref "R13") (pin "1") (pinfunction "1_1") (pintype "passive"))
      (node (ref "U1") (pin "126") (pinfunction "PG11_126") (pintype "passive"))
    )
    (net (code "18") (name "/Ch6Button") (class "Default")
      (node (ref "SW3") (pin "1") (pinfunction "1_1") (pintype "passive"))
    )
    (net (code "19") (name "/Ch6HighLED") (class "Default")
      (node (ref "R22") (pin "1") (pinfunction "1_1") (pintype "passive"))
    )
    (net (code "20") (name "/Ch6LowLED") (class "Default")
      (node (ref "R14") (pin "1") (pinfunction "1_1") (pintype "passive"))
    )
    (net (code "21") (name "/Ch7Button") (class "Default")
      (node (ref "SW7") (pin "1") (pinfunction "1_1") (pintype "passive"))
    )
    (net (code "22") (name "/Ch7HighLED") (class "Default")
      (node (ref "R23") (pin "1") (pinfunction "1_1") (pintype "passive"))
      (node (ref "U1") (pin "50") (pinfunction "PF12_50") (pintype "passive"))
    )
    (net (code "23") (name "/Ch7LowLED") (class "Default")
      (node (ref "R15") (pin "1") (pinfunction "1_1") (pintype "passive"))
      (node (ref "U1") (pin "49") (pinfunction "PF11_49") (pintype "passive"))
    )
    (net (code "24") (name "/Ch8Button") (class "Default")
      (node (ref "SW10") (pin "1") (pinfunction "1_1") (pintype "passive"))
      (node (ref "U1") (pin "54") (pinfunction "PF14_54") (pintype "passive"))
    )
    (net (code "25") (name "/Ch8HighLED") (class "Default")
      (node (ref "R24") (pin "1") (pinfunction "1_1") (pintype "passive"))
      (node (ref "U1") (pin "56") (pinfunction "PG0_56") (pintype "passive"))
    )
    (net (code "26") (name "/Ch8LowLED") (class "Default")
      (node (ref "R16") (pin "1") (pinfunction "1_1") (pintype "passive"))
      (node (ref "U1") (pin "55") (pinfunction "PF15_55") (pintype "passive"))
    )
    (net (code "27") (name "/LED1") (class "Default")
      (node (ref "R38") (pin "1") (pinfunction "1_1") (pintype "passive"))
    )
    (net (code "28") (name "/LED2") (class "Default")
      (node (ref "R39") (pin "1") (pinfunction "1_1") (pintype "passive"))
    )
    (net (code "29") (name "/LED3") (class "Default")
      (node (ref "R40") (pin "1") (pinfunction "1_1") (pintype "passive"))
    )
    (net (code "30") (name "/LevelLED1") (class "Default")
      (node (ref "R25") (pin "1") (pinfunction "1_1") (pintype "passive"))
      (node (ref "U1") (pin "64") (pinfunction "PE11_64") (pintype "passive"))
    )
    (net (code "31") (name "/LevelLED2") (class "Default")
      (node (ref "R26") (pin "1") (pinfunction "1_1") (pintype "passive"))
      (node (ref "U1") (pin "65") (pinfunction "PE12_65") (pintype "passive"))
    )
    (net (code "32") (name "/LevelLED3") (class "Default")
      (node (ref "R27") (pin "1") (pinfunction "1_1") (pintype "passive"))
      (node (ref "U1") (pin "66") (pinfunction "PE13_66") (pintype "passive"))
    )
    (net (code "33") (name "/LevelLED4") (class "Default")
      (node (ref "R28") (pin "1") (pinfunction "1_1") (pintype "passive"))
      (node (ref "U1") (pin "67") (pinfunction "PE14_67") (pintype "passive"))
    )
    (net (code "34") (name "/LevelLED5") (class "Default")
      (node (ref "R29") (pin "1") (pinfunction "1_1") (pintype "passive"))
      (node (ref "U1") (pin "68") (pinfunction "PE15_68") (pintype "passive"))
    )
    (net (code "35") (name "/LevelLED6") (class "Default")
      (node (ref "R30") (pin "1") (pinfunction "1_1") (pintype "passive"))
    )
    (net (code "36") (name "/LevelLED7") (class "Default")
      (node (ref "R31") (pin "1") (pinfunction "1_1") (pintype "passive"))
    )
    (net (code "37") (name "/LevelLED8") (class "Default")
      (node (ref "R32") (pin "1") (pinfunction "1_1") (pintype "passive"))
    )
    (net (code "38") (name "/LevelLED9") (class "Default")
      (node (ref "R34") (pin "1") (pinfunction "1_1") (pintype "passive"))
    )
    (net (code "39") (name "/LevelLED10") (class "Default")
      (node (ref "R35") (pin "1") (pinfunction "1_1") (pintype "passive"))
    )
    (net (code "40") (name "/LevelLED11") (class "Default")
      (node (ref "R36") (pin "1") (pinfunction "1_1") (pintype "passive"))
    )
    (net (code "41") (name "/LevelLED12") (class "Default")
      (node (ref "R37") (pin "1") (pinfunction "1_1") (pintype "passive"))
    )
    (net (code "42") (name "/NRST") (class "Default")
      (node (ref "C13") (pin "1") (pinfunction "1_1") (pintype "passive"))
      (node (ref "J10") (pin "5") (pinfunction "5_5") (pintype "passive"))
      (node (ref "U1") (pin "25") (pinfunction "~{RST}_25") (pintype "passive"))
    )
    (net (code "43") (name "/RotaryCLK") (class "Default")
      (node (ref "SW4") (pin "A") (pinfunction "A_A") (pintype "passive"))
    )
    (net (code "44") (name "/RotaryDT") (class "Default")
      (node (ref "SW4") (pin "B") (pinfunction "B_B") (pintype "passive"))
    )
    (net (code "45") (name "/SWCLK") (class "Default")
      (node (ref "J10") (pin "2") (pinfunction "2_2") (pintype "passive"))
    )
    (net (code "46") (name "/SWIO") (class "Default")
      (node (ref "J10") (pin "4") (pinfunction "4_4") (pintype "passive"))
    )
    (net (code "47") (name "/SetupButton") (class "Default")
      (node (ref "SW1") (pin "1") (pinfunction "1_1") (pintype "passive"))
    )
    (net (code "48") (name "/SetupLED") (class "Default")
      (node (ref "R41") (pin "1") (pinfunction "1_1") (pintype "passive"))
    )
    (net (code "49") (name "/USB_D_N") (class "Default")
      (node (ref "J11") (pin "2") (pinfunction "D-_2") (pintype "passive"))
    )
    (net (code "50") (name "/USB_D_P") (class "Default")
      (node (ref "J11") (pin "3") (pinfunction "D+_3") (pintype "passive"))
    )
    (net (code "51") (name "GND") (class "Default")
      (node (ref "C10") (pin "2") (pinfunction "2_2") (pintype "passive"))
      (node (ref "C11") (pin "2") (pinfunction "2_2") (pintype "passive"))
      (node (ref "C12") (pin "2") (pinfunction "2_2") (pintype "passive"))
      (node (ref "C13") (pin "2") (pinfunction "2_2") (pintype "passive"))
      (node (ref "C14") (pin "2") (pinfunction "2_2") (pintype "passive"))
      (node (ref "C15") (pin "2") (pinfunction "2_2") (pintype "passive"))
      (node (ref "C16") (pin "2") (pinfunction "2_2") (pintype "passive"))
      (node (ref "C17") (pin "2") (pinfunction "2_2") (pintype "passive"))
      (node (ref "C18") (pin "2") (pinfunction "2_2") (pintype "passive"))
      (node (ref "C19") (pin "2") (pinfunction "2_2") (pintype "passive"))
      (node (ref "C20") (pin "2") (pinfunction "2_2") (pintype "passive"))
      (node (ref "C21") (pin "2") (pinfunction "2_2") (pintype "passive"))
      (node (ref "C22") (pin "2") (pinfunction "2_2") (pintype "passive"))
      (node (ref "C23") (pin "2") (pinfunction "2_2") (pintype "passive"))
      (node (ref "C24") (pin "2") (pinfunction "2_2") (pintype "passive"))
      (node (ref "C25") (pin "2") (pinfunction "2_2") (pintype "passive"))
      (node (ref "C26") (pin "2") (pinfunction "2_2") (pintype "passive"))
      (node (ref "C9") (pin "2") (pinfunction "2_2") (pintype "passive"))
      (node (ref "CPW1") (pin "2") (pinfunction "2_2") (pintype "passive"))
      (node (ref "CPW2") (pin "2") (pinfunction "2_2") (pintype "passive"))
      (node (ref "DS1") (pin "2") (pinfunction "K_2") (pintype "passive"))
      (node (ref "DS10") (pin "2") (pinfunction "K_2") (pintype "passive"))
      (node (ref "DS11") (pin "2") (pinfunction "K_2") (pintype "passive"))
      (node (ref "DS12") (pin "2") (pinfunction "K_2") (pintype "passive"))
      (node (ref "DS13") (pin "2") (pinfunction "K_2") (pintype "passive"))
      (node (ref "DS14") (pin "2") (pinfunction "K_2") (pintype "passive"))
      (node (ref "DS15") (pin "2") (pinfunction "K_2") (pintype "passive"))
      (node (ref "DS16") (pin "2") (pinfunction "K_2") (pintype "passive"))
      (node (ref "DS17") (pin "2") (pinfunction "K_2") (pintype "passive"))
      (node (ref "DS18") (pin "2") (pinfunction "K_2") (pintype "passive"))
      (node (ref "DS19") (pin "2") (pinfunction "K_2") (pintype "passive"))
      (node (ref "DS2") (pin "2") (pinfunction "K_2") (pintype "passive"))
      (node (ref "DS20") (pin "2") (pinfunction "K_2") (pintype "passive"))
      (node (ref "DS21") (pin "2") (pinfunction "K_2") (pintype "passive"))
      (node (ref "DS22") (pin "2") (pinfunction "K_2") (pintype "passive"))
      (node (ref "DS23") (pin "2") (pinfunction "K_2") (pintype "passive"))
      (node (ref "DS24") (pin "2") (pinfunction "K_2") (pintype "passive"))
      (node (ref "DS25") (pin "2") (pinfunction "K_2") (pintype "passive"))
      (node (ref "DS26") (pin "2") (pinfunction "K_2") (pintype "passive"))
      (node (ref "DS27") (pin "2") (pinfunction "K_2") (pintype "passive"))
      (node (ref "DS28") (pin "2") (pinfunction "K_2") (pintype "passive"))
      (node (ref "DS29") (pin "2") (pinfunction "K_2") (pintype "passive"))
      (node (ref "DS3") (pin "2") (pinfunction "K_2") (pintype "passive"))
      (node (ref "DS30") (pin "2") (pinfunction "K_2") (pintype "passive"))
      (node (ref "DS31") (pin "2") (pinfunction "K_2") (pintype "passive"))
      (node (ref "DS32") (pin "2") (pinfunction "K_2") (pintype "passive"))
      (node (ref "DS4") (pin "2") (pinfunction "K_2") (pintype "passive"))
      (node (ref "DS5") (pin "2") (pinfunction "K_2") (pintype "passive"))
      (node (ref "DS6") (pin "2") (pinfunction "K_2") (pintype "passive"))
      (node (ref "DS7") (pin "2") (pinfunction "K_2") (pintype "passive"))
      (node (ref "DS8") (pin "2") (pinfunction "K_2") (pintype "passive"))
      (node (ref "DS9") (pin "2") (pinfunction "K_2") (pintype "passive"))
      (node (ref "J10") (pin "3") (pinfunction "3_3") (pintype "passive"))
      (node (ref "J11") (pin "10") (pinfunction "SHLD5_10") (pintype "passive"))
      (node (ref "J11") (pin "11") (pinfunction "SHLD6_11") (pintype "passive"))
      (node (ref "J11") (pin "5") (pinfunction "GND_5") (pintype "passive"))
      (node (ref "J11") (pin "6") (pinfunction "SHLD1_6") (pintype "passive"))
      (node (ref "J11") (pin "7") (pinfunction "SHLD2_7") (pintype "passive"))
      (node (ref "J11") (pin "8") (pinfunction "SHLD3_8") (pintype "passive"))
      (node (ref "J11") (pin "9") (pinfunction "SHLD4_9") (pintype "passive"))
      (node (ref "J9") (pin "1") (pinfunction "1_1") (pintype "passive"))
      (node (ref "R33") (pin "2") (pinfunction "2_2") (pintype "passive"))
      (node (ref "SW1") (pin "3") (pinfunction "3_3") (pintype "passive"))
      (node (ref "SW10") (pin "3") (pinfunction "3_3") (pintype "passive"))
      (node (ref "SW2") (pin "3") (pinfunction "3_3") (pintype "passive"))
      (node (ref "SW3") (pin "3") (pinfunction "3_3") (pintype "passive"))
      (node (ref "SW4") (pin "C") (pinfunction "C_C") (pintype "passive"))
      (node (ref "SW5") (pin "3") (pinfunction "3_3") (pintype "passive"))
      (node (ref "SW6") (pin "3") (pinfunction "3_3") (pintype "passive"))
      (node (ref "SW7") (pin "3") (pinfunction "3_3") (pintype "passive"))
      (node (ref "SW8") (pin "3") (pinfunction "3_3") (pintype "passive"))
      (node (ref "SW9") (pin "3") (pinfunction "3_3") (pintype "passive"))
      (node (ref "U1") (pin "107") (pinfunction "VSS_107") (pintype "passive"))
      (node (ref "U1") (pin "120") (pinfunction "VSS_120") (pintype "passive"))
      (node (ref "U1") (pin "16") (pinfunction "VSS_16") (pintype "passive"))
      (node (ref "U1") (pin "31") (pinfunction "VSSA_31") (pintype "passive"))
      (node (ref "U1") (pin "38") (pinfunction "VSS_38") (pintype "passive"))
      (node (ref "U1") (pin "51") (pinfunction "VSS_51") (pintype "passive"))
      (node (ref "U1") (pin "61") (pinfunction "VSS_61") (pintype "passive"))
      (node (ref "U1") (pin "83") (pinfunction "VSS_83") (pintype "passive"))
      (node (ref "U1") (pin "94") (pinfunction "VSS_94") (pintype "passive"))
      (node (ref "U6") (pin "1") (pinfunction "GND_1") (pintype "power_in"))
    )
    (net (code "52") (name "Net-(C27-Pad1)") (class "Default")
      (node (ref "C27") (pin "1") (pinfunction "1_1") (pintype "passive"))
      (node (ref "R42") (pin "1") (pinfunction "1_1") (pintype "passive"))
      (node (ref "SW1") (pin "2") (pinfunction "2_2") (pintype "passive"))
    )
    (net (code "53") (name "Net-(C27-Pad2)") (class "Default")
      (node (ref "C27") (pin "2") (pinfunction "2_2") (pintype "passive"))
      (node (ref "SW1") (pin "4") (pinfunction "4_4") (pintype "passive"))
    )
    (net (code "54") (name "Net-(C28-Pad1)") (class "Default")
      (node (ref "C28") (pin "1") (pinfunction "1_1") (pintype "passive"))
      (node (ref "R43") (pin "1") (pinfunction "1_1") (pintype "passive"))
      (node (ref "SW2") (pin "2") (pinfunction "2_2") (pintype "passive"))
    )
    (net (code "55") (name "Net-(C28-Pad2)") (class "Default")
      (node (ref "C28") (pin "2") (pinfunction "2_2") (pintype "passive"))
      (node (ref "SW2") (pin "4") (pinfunction "4_4") (pintype "passive"))
    )
    (net (code "56") (name "Net-(C29-Pad1)") (class "Default")
      (node (ref "C29") (pin "1") (pinfunction "1_1") (pintype "passive"))
      (node (ref "R44") (pin "1") (pinfunction "1_1") (pintype "passive"))
      (node (ref "SW3") (pin "2") (pinfunction "2_2") (pintype "passive"))
    )
    (net (code "57") (name "Net-(C29-Pad2)") (class "Default")
      (node (ref "C29") (pin "2") (pinfunction "2_2") (pintype "passive"))
      (node (ref "SW3") (pin "4") (pinfunction "4_4") (pintype "passive"))
    )
    (net (code "58") (name "Net-(C30-Pad1)") (class "Default")
      (node (ref "C30") (pin "1") (pinfunction "1_1") (pintype "passive"))
      (node (ref "R45") (pin "1") (pinfunction "1_1") (pintype "passive"))
      (node (ref "SW5") (pin "2") (pinfunction "2_2") (pintype "passive"))
    )
    (net (code "59") (name "Net-(C30-Pad2)") (class "Default")
      (node (ref "C30") (pin "2") (pinfunction "2_2") (pintype "passive"))
      (node (ref "SW5") (pin "4") (pinfunction "4_4") (pintype "passive"))
    )
    (net (code "60") (name "Net-(C31-Pad1)") (class "Default")
      (node (ref "C31") (pin "1") (pinfunction "1_1") (pintype "passive"))
      (node (ref "R46") (pin "1") (pinfunction "1_1") (pintype "passive"))
      (node (ref "SW6") (pin "2") (pinfunction "2_2") (pintype "passive"))
    )
    (net (code "61") (name "Net-(C31-Pad2)") (class "Default")
      (node (ref "C31") (pin "2") (pinfunction "2_2") (pintype "passive"))
      (node (ref "SW6") (pin "4") (pinfunction "4_4") (pintype "passive"))
    )
    (net (code "62") (name "Net-(C32-Pad1)") (class "Default")
      (node (ref "C32") (pin "1") (pinfunction "1_1") (pintype "passive"))
      (node (ref "R47") (pin "1") (pinfunction "1_1") (pintype "passive"))
      (node (ref "SW7") (pin "2") (pinfunction "2_2") (pintype "passive"))
    )
    (net (code "63") (name "Net-(C32-Pad2)") (class "Default")
      (node (ref "C32") (pin "2") (pinfunction "2_2") (pintype "passive"))
      (node (ref "SW7") (pin "4") (pinfunction "4_4") (pintype "passive"))
    )
    (net (code "64") (name "Net-(C33-Pad1)") (class "Default")
      (node (ref "C33") (pin "1") (pinfunction "1_1") (pintype "passive"))
      (node (ref "R48") (pin "1") (pinfunction "1_1") (pintype "passive"))
      (node (ref "SW8") (pin "2") (pinfunction "2_2") (pintype "passive"))
    )
    (net (code "65") (name "Net-(C33-Pad2)") (class "Default")
      (node (ref "C33") (pin "2") (pinfunction "2_2") (pintype "passive"))
      (node (ref "SW8") (pin "4") (pinfunction "4_4") (pintype "passive"))
    )
    (net (code "66") (name "Net-(C34-Pad1)") (class "Default")
      (node (ref "C34") (pin "1") (pinfunction "1_1") (pintype "passive"))
      (node (ref "R49") (pin "1") (pinfunction "1_1") (pintype "passive"))
      (node (ref "SW9") (pin "2") (pinfunction "2_2") (pintype "passive"))
    )
    (net (code "67") (name "Net-(C34-Pad2)") (class "Default")
      (node (ref "C34") (pin "2") (pinfunction "2_2") (pintype "passive"))
      (node (ref "SW9") (pin "4") (pinfunction "4_4") (pintype "passive"))
    )
    (net (code "68") (name "Net-(C35-Pad1)") (class "Default")
      (node (ref "C35") (pin "1") (pinfunction "1_1") (pintype "passive"))
      (node (ref "R50") (pin "1") (pinfunction "1_1") (pintype "passive"))
      (node (ref "SW10") (pin "2") (pinfunction "2_2") (pintype "passive"))
    )
    (net (code "69") (name "Net-(C35-Pad2)") (class "Default")
      (node (ref "C35") (pin "2") (pinfunction "2_2") (pintype "passive"))
      (node (ref "SW10") (pin "4") (pinfunction "4_4") (pintype "passive"))
    )
    (net (code "70") (name "Net-(DS1-A)") (class "Default")
      (node (ref "DS1") (pin "1") (pinfunction "A_1") (pintype "passive"))
      (node (ref "R9") (pin "2") (pinfunction "2_2") (pintype "passive"))
    )
    (net (code "71") (name "Net-(DS2-A)") (class "Default")
      (node (ref "DS2") (pin "1") (pinfunction "A_1") (pintype "passive"))
      (node (ref "R10") (pin "2") (pinfunction "2_2") (pintype "passive"))
    )
    (net (code "72") (name "Net-(DS3-A)") (class "Default")
      (node (ref "DS3") (pin "1") (pinfunction "A_1") (pintype "passive"))
      (node (ref "R11") (pin "2") (pinfunction "2_2") (pintype "passive"))
    )
    (net (code "73") (name "Net-(DS4-A)") (class "Default")
      (node (ref "DS4") (pin "1") (pinfunction "A_1") (pintype "passive"))
      (node (ref "R12") (pin "2") (pinfunction "2_2") (pintype "passive"))
    )
    (net (code "74") (name "Net-(DS5-A)") (class "Default")
      (node (ref "DS5") (pin "1") (pinfunction "A_1") (pintype "passive"))
      (node (ref "R13") (pin "2") (pinfunction "2_2") (pintype "passive"))
    )
    (net (code "75") (name "Net-(DS6-A)") (class "Default")
      (node (ref "DS6") (pin "1") (pinfunction "A_1") (pintype "passive"))
      (node (ref "R14") (pin "2") (pinfunction "2_2") (pintype "passive"))
    )
    (net (code "76") (name "Net-(DS7-A)") (class "Default")
      (node (ref "DS7") (pin "1") (pinfunction "A_1") (pintype "passive"))
      (node (ref "R15") (pin "2") (pinfunction "2_2") (pintype "passive"))
    )
    (net (code "77") (name "Net-(DS8-A)") (class "Default")
      (node (ref "DS8") (pin "1") (pinfunction "A_1") (pintype "passive"))
      (node (ref "R16") (pin "2") (pinfunction "2_2") (pintype "passive"))
    )
    (net (code "78") (name "Net-(DS9-A)") (class "Default")
      (node (ref "DS9") (pin "1") (pinfunction "A_1") (pintype "passive"))
      (node (ref "R17") (pin "2") (pinfunction "2_2") (pintype "passive"))
    )
    (net (code "79") (name "Net-(DS10-A)") (class "Default")
      (node (ref "DS10") (pin "1") (pinfunction "A_1") (pintype "passive"))
      (node (ref "R18") (pin "2") (pinfunction "2_2") (pintype "passive"))
    )
    (net (code "80") (name "Net-(DS11-A)") (class "Default")
      (node (ref "DS11") (pin "1") (pinfunction "A_1") (pintype "passive"))
      (node (ref "R19") (pin "2") (pinfunction "2_2") (pintype "passive"))
    )
    (net (code "81") (name "Net-(DS12-A)") (class "Default")
      (node (ref "DS12") (pin "1") (pinfunction "A_1") (pintype "passive"))
      (node (ref "R20") (pin "2") (pinfunction "2_2") (pintype "passive"))
    )
    (net (code "82") (name "Net-(DS13-A)") (class "Default")
      (node (ref "DS13") (pin "1") (pinfunction "A_1") (pintype "passive"))
      (node (ref "R21") (pin "2") (pinfunction "2_2") (pintype "passive"))
    )
    (net (code "83") (name "Net-(DS14-A)") (class "Default")
      (node (ref "DS14") (pin "1") (pinfunction "A_1") (pintype "passive"))
      (node (ref "R22") (pin "2") (pinfunction "2_2") (pintype "passive"))
    )
    (net (code "84") (name "Net-(DS15-A)") (class "Default")
      (node (ref "DS15") (pin "1") (pinfunction "A_1") (pintype "passive"))
      (node (ref "R23") (pin "2") (pinfunction "2_2") (pintype "passive"))
    )
    (net (code "85") (name "Net-(DS16-A)") (class "Default")
      (node (ref "DS16") (pin "1") (pinfunction "A_1") (pintype "passive"))
      (node (ref "R24") (pin "2") (pinfunction "2_2") (pintype "passive"))
    )
    (net (code "86") (name "Net-(DS17-A)") (class "Default")
      (node (ref "DS17") (pin "1") (pinfunction "A_1") (pintype "passive"))
      (node (ref "R25") (pin "2") (pinfunction "2_2") (pintype "passive"))
    )
    (net (code "87") (name "Net-(DS18-A)") (class "Default")
      (node (ref "DS18") (pin "1") (pinfunction "A_1") (pintype "passive"))
      (node (ref "R26") (pin "2") (pinfunction "2_2") (pintype "passive"))
    )
    (net (code "88") (name "Net-(DS19-A)") (class "Default")
      (node (ref "DS19") (pin "1") (pinfunction "A_1") (pintype "passive"))
      (node (ref "R27") (pin "2") (pinfunction "2_2") (pintype "passive"))
    )
    (net (code "89") (name "Net-(DS20-A)") (class "Default")
      (node (ref "DS20") (pin "1") (pinfunction "A_1") (pintype "passive"))
      (node (ref "R28") (pin "2") (pinfunction "2_2") (pintype "passive"))
    )
    (net (code "90") (name "Net-(DS21-A)") (class "Default")
      (node (ref "DS21") (pin "1") (pinfunction "A_1") (pintype "passive"))
      (node (ref "R29") (pin "2") (pinfunction "2_2") (pintype "passive"))
    )
    (net (code "91") (name "Net-(DS22-A)") (class "Default")
      (node (ref "DS22") (pin "1") (pinfunction "A_1") (pintype "passive"))
      (node (ref "R30") (pin "2") (pinfunction "2_2") (pintype "passive"))
    )
    (net (code "92") (name "Net-(DS23-A)") (class "Default")
      (node (ref "DS23") (pin "1") (pinfunction "A_1") (pintype "passive"))
      (node (ref "R31") (pin "2") (pinfunction "2_2") (pintype "passive"))
    )
    (net (code "93") (name "Net-(DS24-A)") (class "Default")
      (node (ref "DS24") (pin "1") (pinfunction "A_1") (pintype "passive"))
      (node (ref "R32") (pin "2") (pinfunction "2_2") (pintype "passive"))
    )
    (net (code "94") (name "Net-(DS25-A)") (class "Default")
      (node (ref "DS25") (pin "1") (pinfunction "A_1") (pintype "passive"))
      (node (ref "R34") (pin "2") (pinfunction "2_2") (pintype "passive"))
    )
    (net (code "95") (name "Net-(DS26-A)") (class "Default")
      (node (ref "DS26") (pin "1") (pinfunction "A_1") (pintype "passive"))
      (node (ref "R35") (pin "2") (pinfunction "2_2") (pintype "passive"))
    )
    (net (code "96") (name "Net-(DS27-A)") (class "Default")
      (node (ref "DS27") (pin "1") (pinfunction "A_1") (pintype "passive"))
      (node (ref "R36") (pin "2") (pinfunction "2_2") (pintype "passive"))
    )
    (net (code "97") (name "Net-(DS28-A)") (class "Default")
      (node (ref "DS28") (pin "1") (pinfunction "A_1") (pintype "passive"))
      (node (ref "R37") (pin "2") (pinfunction "2_2") (pintype "passive"))
    )
    (net (code "98") (name "Net-(DS29-A)") (class "Default")
      (node (ref "DS29") (pin "1") (pinfunction "A_1") (pintype "passive"))
      (node (ref "R38") (pin "2") (pinfunction "2_2") (pintype "passive"))
    )
    (net (code "99") (name "Net-(DS30-A)") (class "Default")
      (node (ref "DS30") (pin "1") (pinfunction "A_1") (pintype "passive"))
      (node (ref "R39") (pin "2") (pinfunction "2_2") (pintype "passive"))
    )
    (net (code "100") (name "Net-(DS31-A)") (class "Default")
      (node (ref "DS31") (pin "1") (pinfunction "A_1") (pintype "passive"))
      (node (ref "R40") (pin "2") (pinfunction "2_2") (pintype "passive"))
    )
    (net (code "101") (name "Net-(DS32-A)") (class "Default")
      (node (ref "DS32") (pin "1") (pinfunction "A_1") (pintype "passive"))
      (node (ref "R41") (pin "2") (pinfunction "2_2") (pintype "passive"))
    )
    (net (code "102") (name "Net-(U1B-PH0)") (class "Default")
      (node (ref "C10") (pin "1") (pinfunction "1_1") (pintype "passive"))
      (node (ref "U1") (pin "23") (pinfunction "PH0_23") (pintype "passive"))
      (node (ref "Y1") (pin "2") (pinfunction "2_2") (pintype "passive"))
    )
    (net (code "103") (name "Net-(U1B-PH1)") (class "Default")
      (node (ref "C9") (pin "1") (pinfunction "1_1") (pintype "passive"))
      (node (ref "U1") (pin "24") (pinfunction "PH1_24") (pintype "passive"))
      (node (ref "Y1") (pin "1") (pinfunction "1_1") (pintype "passive"))
    )
    (net (code "104") (name "Net-(U1C-BOOT0)") (class "Default")
      (node (ref "R33") (pin "1") (pinfunction "1_1") (pintype "passive"))
      (node (ref "U1") (pin "138") (pinfunction "BOOT0_138") (pintype "bidirectional"))
    )
    (net (code "105") (name "Net-(U1C-VCAP_1)") (class "Default")
      (node (ref "C11") (pin "1") (pinfunction "1_1") (pintype "passive"))
      (node (ref "U1") (pin "71") (pinfunction "VCAP_1_71") (pintype "passive"))
    )
    (net (code "106") (name "Net-(U1C-VCAP_2)") (class "Default")
      (node (ref "C12") (pin "1") (pinfunction "1_1") (pintype "passive"))
      (node (ref "U1") (pin "106") (pinfunction "VCAP_2_106") (pintype "passive"))
    )
    (net (code "107") (name "Net-(U1C-VDDA)") (class "Default")
      (node (ref "FB1") (pin "2") (pinfunction "2_2") (pintype "passive"))
      (node (ref "U1") (pin "32") (pinfunction "VREF+_32") (pintype "passive"))
      (node (ref "U1") (pin "33") (pinfunction "VDDA_33") (pintype "passive"))
    )
    (net (code "108") (name "unconnected-(J11-ID-Pad4)") (class "Default")
      (node (ref "J11") (pin "4") (pinfunction "ID_4") (pintype "passive+no_connect"))
    )
    (net (code "109") (name "unconnected-(J11-VBUS-Pad1)") (class "Default")
      (node (ref "J11") (pin "1") (pinfunction "VBUS_1") (pintype "passive+no_connect"))
    )
    (net (code "110") (name "unconnected-(J12-Pad1)") (class "Default")
      (node (ref "J12") (pin "1") (pinfunction "1_1") (pintype "passive"))
    )
    (net (code "111") (name "unconnected-(J12-Pad2)") (class "Default")
      (node (ref "J12") (pin "2") (pinfunction "2_2") (pintype "passive"))
    )
    (net (code "112") (name "unconnected-(SW4B-MNT_1-Pad3)") (class "Default")
      (node (ref "SW4") (pin "3") (pinfunction "MNT_1_3") (pintype "passive+no_connect"))
    )
    (net (code "113") (name "unconnected-(SW4B-MNT_2-Pad4)") (class "Default")
      (node (ref "SW4") (pin "4") (pinfunction "MNT_2_4") (pintype "passive+no_connect"))
    )
    (net (code "114") (name "unconnected-(U1B-PE0-Pad141)") (class "Default")
      (node (ref "U1") (pin "141") (pinfunction "PE0_141") (pintype "bidirectional"))
    )
    (net (code "115") (name "unconnected-(U1B-PE1-Pad142)") (class "Default")
      (node (ref "U1") (pin "142") (pinfunction "PE1_142") (pintype "power_in"))
    )
    (net (code "116") (name "unconnected-(U1B-PE2-Pad1)") (class "Default")
      (node (ref "U1") (pin "1") (pinfunction "PE2_1") (pintype "passive"))
    )
    (net (code "117") (name "unconnected-(U1B-PE6-Pad5)") (class "Default")
      (node (ref "U1") (pin "5") (pinfunction "PE6_5") (pintype "passive"))
    )
    (net (code "118") (name "unconnected-(U1B-PE7-Pad58)") (class "Default")
      (node (ref "U1") (pin "58") (pinfunction "PE7_58") (pintype "passive"))
    )
    (net (code "119") (name "unconnected-(U1B-PE8-Pad59)") (class "Default")
      (node (ref "U1") (pin "59") (pinfunction "PE8_59") (pintype "passive"))
    )
    (net (code "120") (name "unconnected-(U1B-PE9-Pad60)") (class "Default")
      (node (ref "U1") (pin "60") (pinfunction "PE9_60") (pintype "passive"))
    )
    (net (code "121") (name "unconnected-(U1B-PE10-Pad63)") (class "Default")
      (node (ref "U1") (pin "63") (pinfunction "PE10_63") (pintype "passive"))
    )
    (net (code "122") (name "unconnected-(U1B-PF0-Pad10)") (class "Default")
      (node (ref "U1") (pin "10") (pinfunction "PF0_10") (pintype "passive"))
    )
    (net (code "123") (name "unconnected-(U1B-PF1-Pad11)") (class "Default")
      (node (ref "U1") (pin "11") (pinfunction "PF1_11") (pintype "passive"))
    )
    (net (code "124") (name "unconnected-(U1B-PF5-Pad15)") (class "Default")
      (node (ref "U1") (pin "15") (pinfunction "PF5_15") (pintype "passive"))
    )
    (net (code "125") (name "unconnected-(U1B-PF6-Pad18)") (class "Default")
      (node (ref "U1") (pin "18") (pinfunction "PF6_18") (pintype "passive"))
    )
    (net (code "126") (name "unconnected-(U1B-PF7-Pad19)") (class "Default")
      (node (ref "U1") (pin "19") (pinfunction "PF7_19") (pintype "passive"))
    )
    (net (code "127") (name "unconnected-(U1B-PF8-Pad20)") (class "Default")
      (node (ref "U1") (pin "20") (pinfunction "PF8_20") (pintype "passive"))
    )
    (net (code "128") (name "unconnected-(U1B-PF9-Pad21)") (class "Default")
      (node (ref "U1") (pin "21") (pinfunction "PF9_21") (pintype "passive"))
    )
    (net (code "129") (name "unconnected-(U1B-PF10-Pad22)") (class "Default")
      (node (ref "U1") (pin "22") (pinfunction "PF10_22") (pintype "passive"))
    )
    (net (code "130") (name "unconnected-(U1B-PF13-Pad53)") (class "Default")
      (node (ref "U1") (pin "53") (pinfunction "PF13_53") (pintype "passive"))
    )
    (net (code "131") (name "unconnected-(U1B-PG1-Pad57)") (class "Default")
      (node (ref "U1") (pin "57") (pinfunction "PG1_57") (pintype "passive"))
    )
    (net (code "132") (name "unconnected-(U1B-PG2-Pad87)") (class "Default")
      (node (ref "U1") (pin "87") (pinfunction "PG2_87") (pintype "passive"))
    )
    (net (code "133") (name "unconnected-(U1B-PG3-Pad88)") (class "Default")
      (node (ref "U1") (pin "88") (pinfunction "PG3_88") (pintype "passive"))
    )
    (net (code "134") (name "unconnected-(U1B-PG4-Pad89)") (class "Default")
      (node (ref "U1") (pin "89") (pinfunction "PG4_89") (pintype "passive"))
    )
    (net (code "135") (name "unconnected-(U1B-PG8-Pad93)") (class "Default")
      (node (ref "U1") (pin "93") (pinfunction "PG8_93") (pintype "passive"))
    )
    (net (code "136") (name "unconnected-(U1B-PG9-Pad124)") (class "Default")
      (node (ref "U1") (pin "124") (pinfunction "PG9_124") (pintype "passive"))
    )
    (net (code "137") (name "unconnected-(U1B-PG13-Pad128)") (class "Default")
      (node (ref "U1") (pin "128") (pinfunction "PG13_128") (pintype "bidirectional"))
    )
    (net (code "138") (name "unconnected-(U1B-PG14-Pad129)") (class "Default")
      (node (ref "U1") (pin "129") (pinfunction "PG14_129") (pintype "bidirectional"))
    )
    (net (code "139") (name "unconnected-(U1B-PG15-Pad132)") (class "Default")
      (node (ref "U1") (pin "132") (pinfunction "PG15_132") (pintype "power_in"))
    )
    (net (code "140") (name "unconnected-(U1C-PDR_ON-Pad143)") (class "Default")
      (node (ref "U1") (pin "143") (pinfunction "PDR_ON_143") (pintype "power_in"))
    )
    (net (code "141") (name "unconnected-(U1C-VDD-Pad131)") (class "Default")
      (node (ref "U1") (pin "131") (pinfunction "VDD_131") (pintype "bidirectional+no_connect"))
    )
    (net (code "142") (name "unconnected-(U1C-VDD-Pad144)") (class "Default")
      (node (ref "U1") (pin "144") (pinfunction "VDD_144") (pintype "bidirectional+no_connect"))
    )
    (net (code "143") (name "unconnected-(U1C-VSS-Pad130)") (class "Default")
      (node (ref "U1") (pin "130") (pinfunction "VSS_130") (pintype "bidirectional+no_connect"))
    )
  )
)
